# microfloat.net
KiCad netlist of a schematic drawn in EAGLE
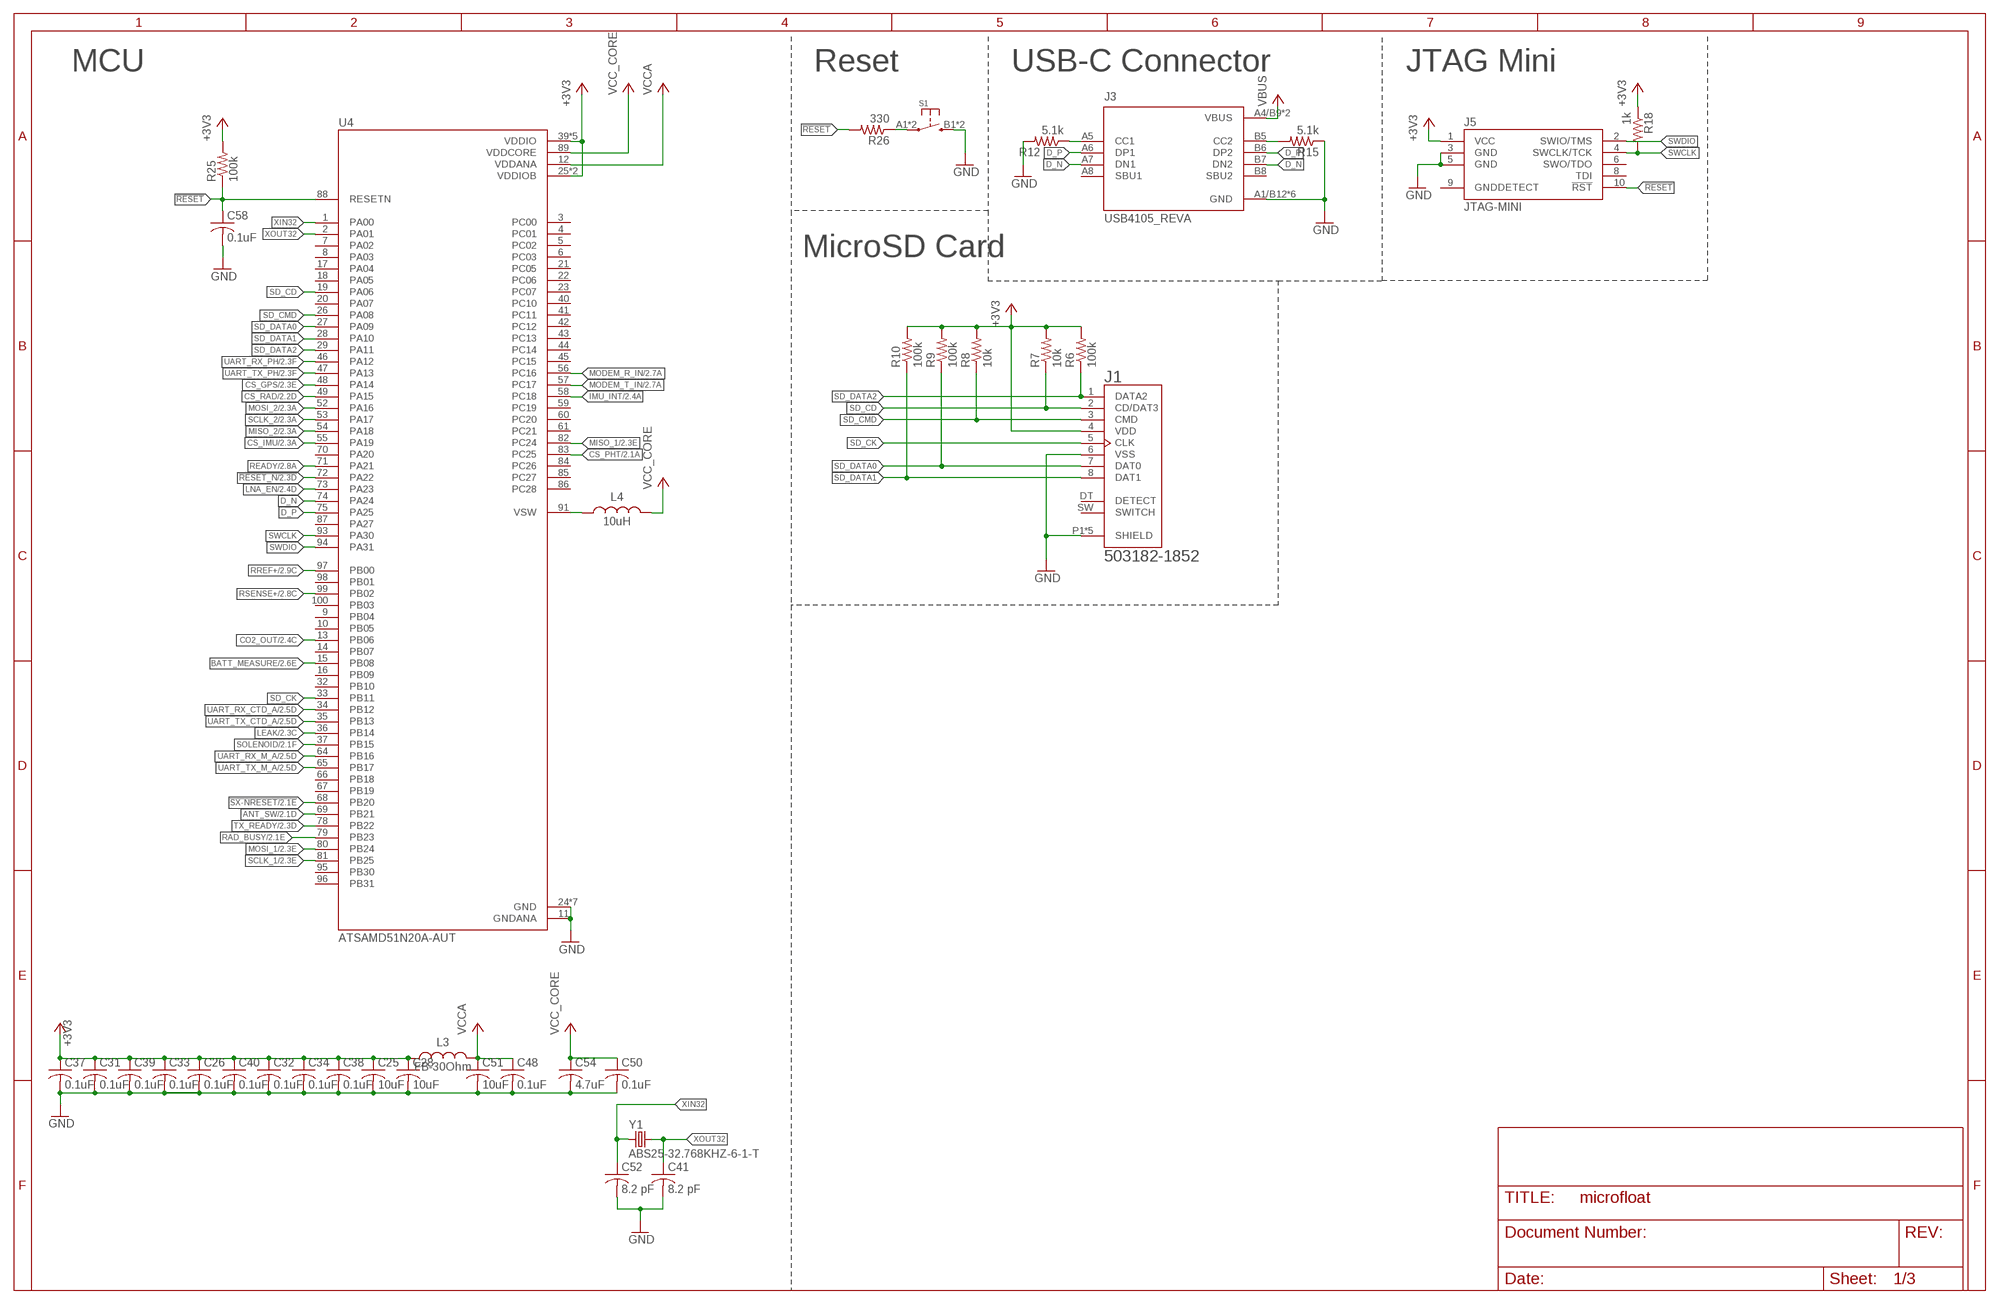
[diagram p0: schematic, sheet 1]
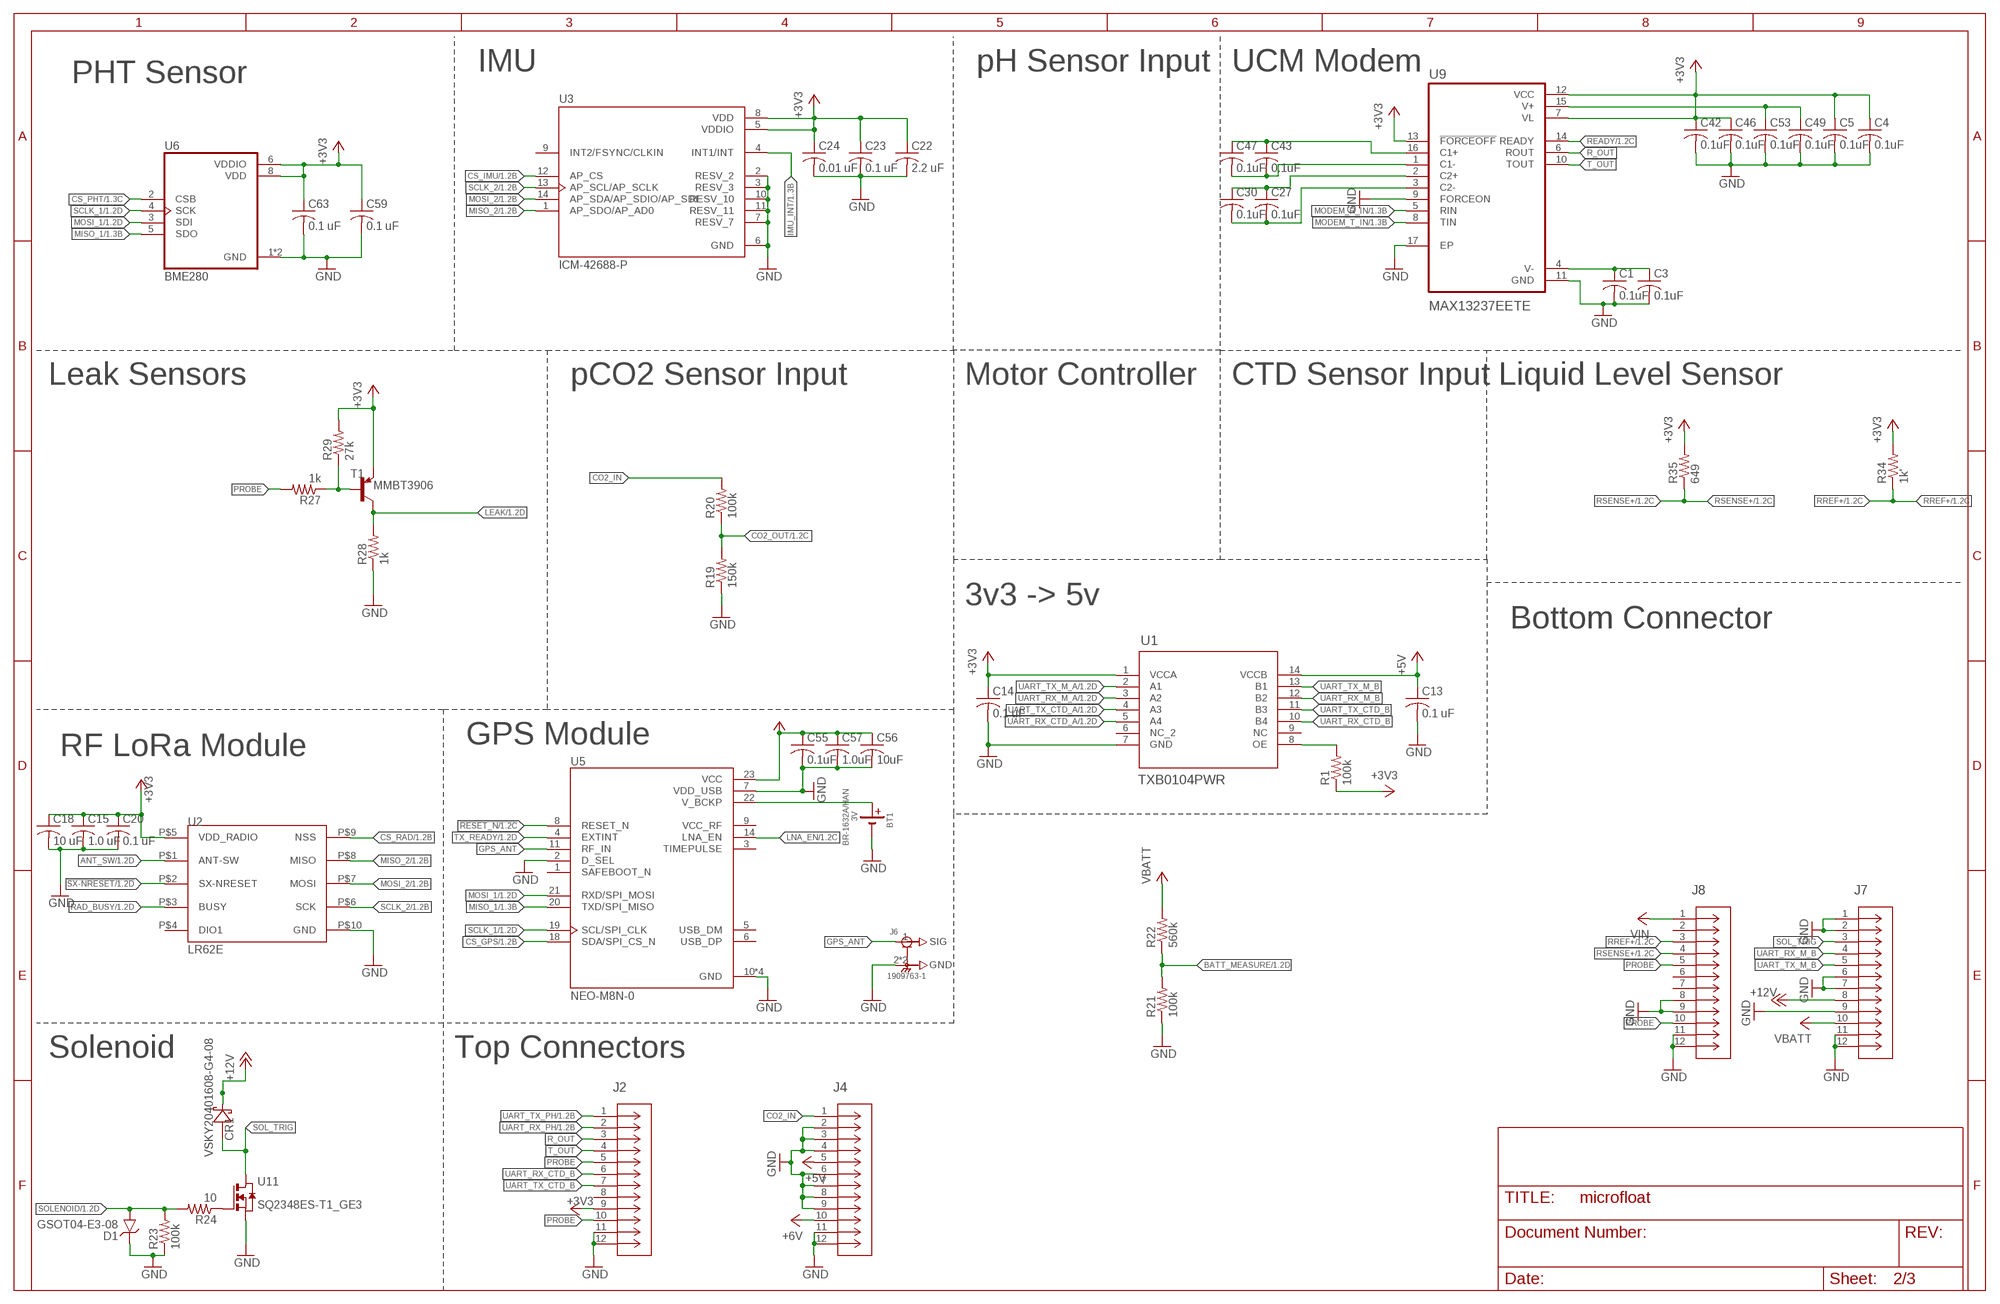
[diagram p1: schematic, sheet 2]
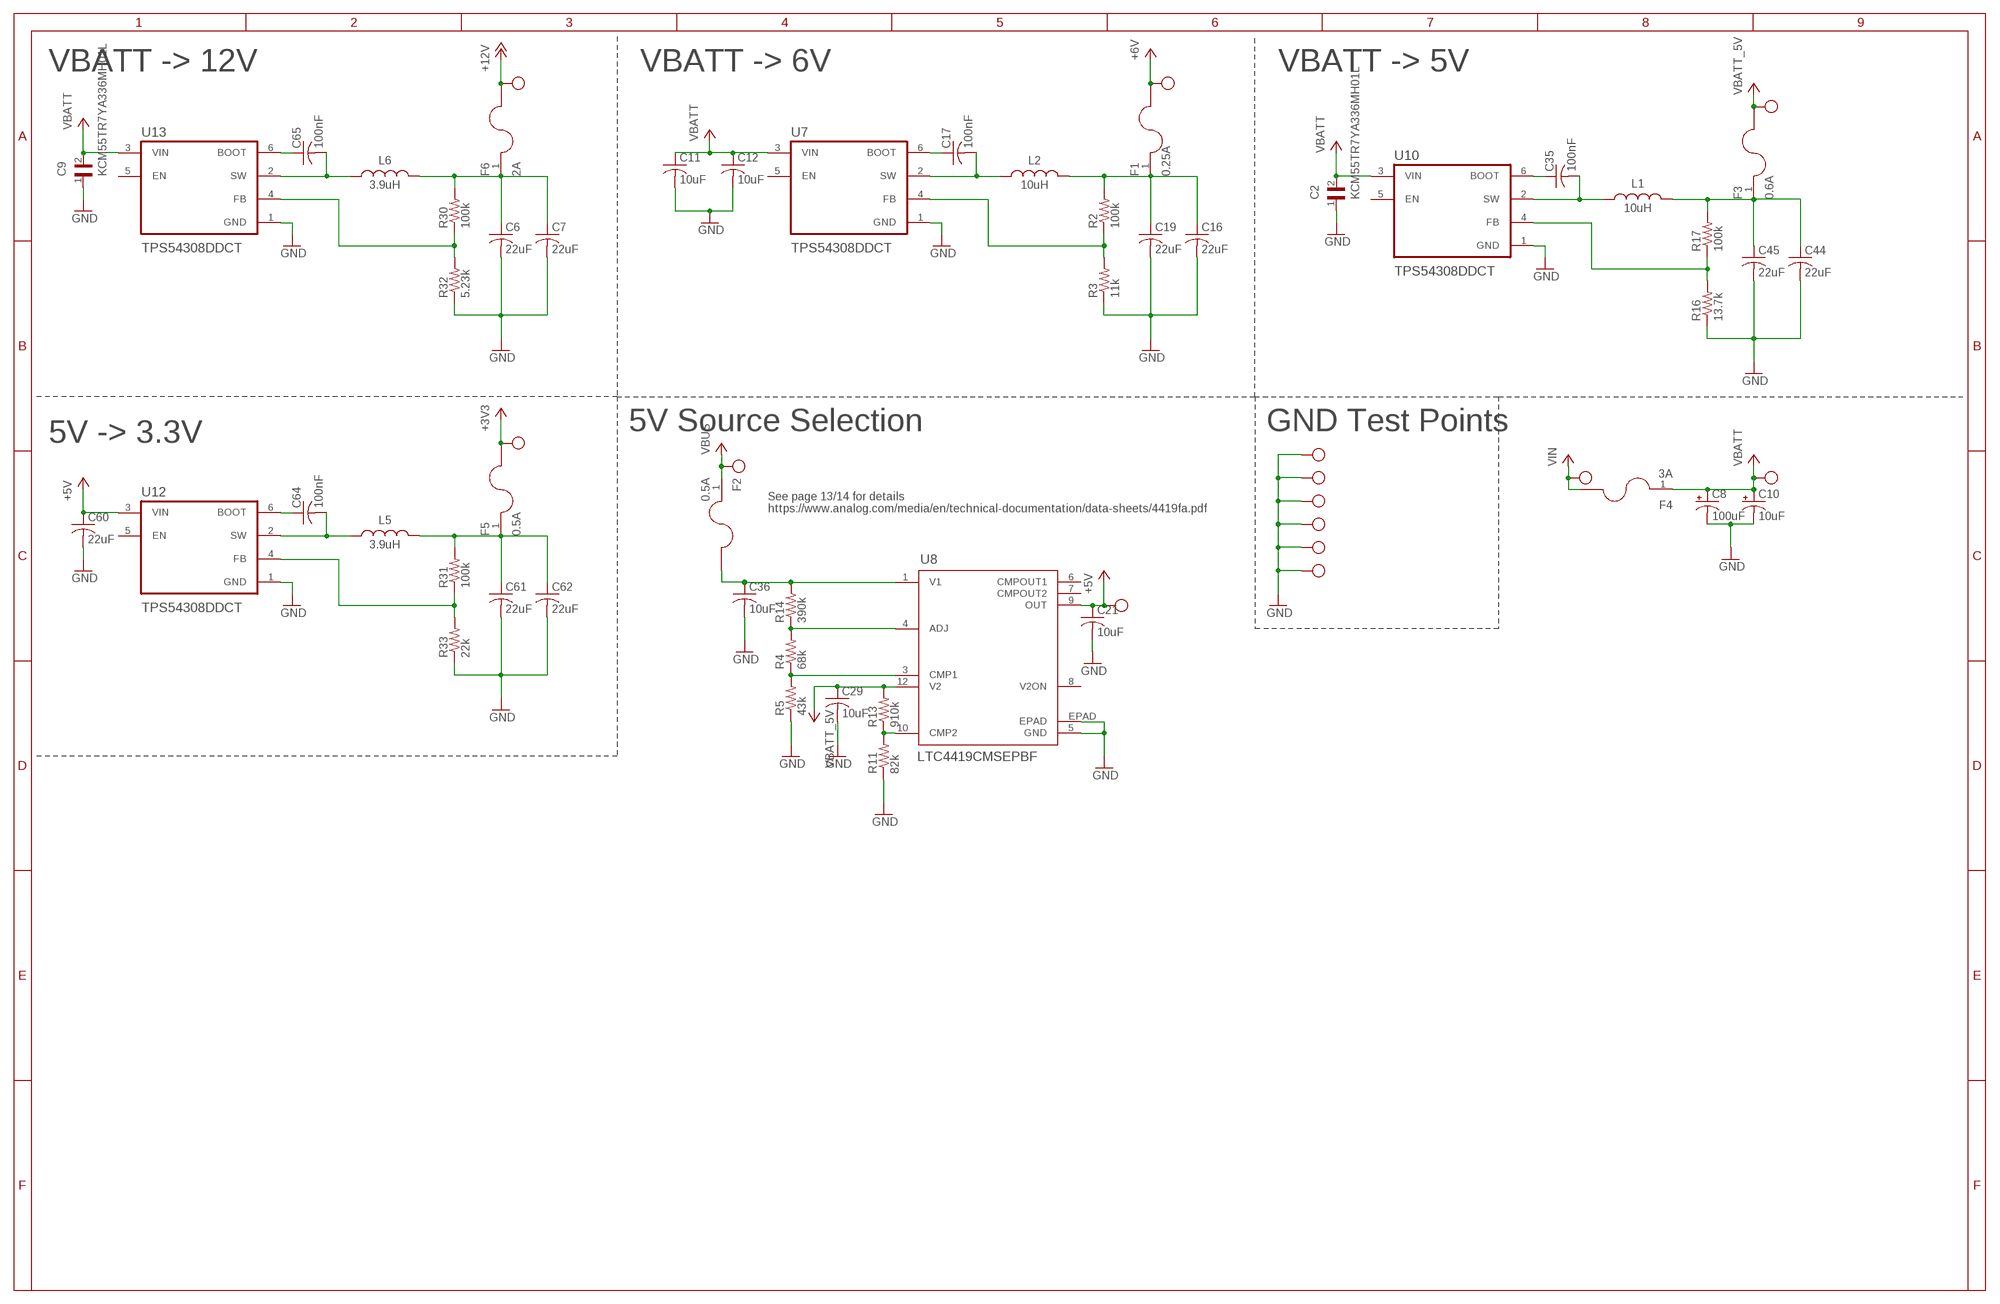
[diagram p2: schematic, sheet 3]

(export (version "E")
  (design (tool "Eeschema 10.0.6"))
  (components
    (comp (ref "C25")
      (value "10uF")
      (footprint "eagle-import:C0805")
      (fields (field (name "TOLERANCE") "5%") (field (name "VOLTAGE") "10V"))
      (libsource (lib "eagle-import") (part "C-USC0805"))
    )
    (comp (ref "C26")
      (value "0.1uF")
      (footprint "eagle-import:C0603")
      (fields (field (name "TOLERANCE") "5%") (field (name "VOLTAGE") "10V"))
      (libsource (lib "eagle-import") (part "C-USC0603"))
    )
    (comp (ref "C28")
      (value "10uF")
      (footprint "eagle-import:C0805")
      (fields (field (name "TOLERANCE") "5%") (field (name "VOLTAGE") "10V"))
      (libsource (lib "eagle-import") (part "C-USC0805"))
    )
    (comp (ref "C31")
      (value "0.1uF")
      (footprint "eagle-import:C0603")
      (fields (field (name "TOLERANCE") "5%") (field (name "VOLTAGE") "10V"))
      (libsource (lib "eagle-import") (part "C-USC0603"))
    )
    (comp (ref "C32")
      (value "0.1uF")
      (footprint "eagle-import:C0603")
      (fields (field (name "TOLERANCE") "5%") (field (name "VOLTAGE") "10V"))
      (libsource (lib "eagle-import") (part "C-USC0603"))
    )
    (comp (ref "C33")
      (value "0.1uF")
      (footprint "eagle-import:C0603")
      (fields (field (name "TOLERANCE") "5%") (field (name "VOLTAGE") "10V"))
      (libsource (lib "eagle-import") (part "C-USC0603"))
    )
    (comp (ref "C34")
      (value "0.1uF")
      (footprint "eagle-import:C0603")
      (fields (field (name "TOLERANCE") "5%") (field (name "VOLTAGE") "10V"))
      (libsource (lib "eagle-import") (part "C-USC0603"))
    )
    (comp (ref "C37")
      (value "0.1uF")
      (footprint "eagle-import:C0603")
      (fields (field (name "TOLERANCE") "5%") (field (name "VOLTAGE") "10V"))
      (libsource (lib "eagle-import") (part "C-USC0603"))
    )
    (comp (ref "C38")
      (value "0.1uF")
      (footprint "eagle-import:C0603")
      (fields (field (name "TOLERANCE") "5%") (field (name "VOLTAGE") "10V"))
      (libsource (lib "eagle-import") (part "C-USC0603"))
    )
    (comp (ref "C39")
      (value "0.1uF")
      (footprint "eagle-import:C0603")
      (fields (field (name "TOLERANCE") "5%") (field (name "VOLTAGE") "10V"))
      (libsource (lib "eagle-import") (part "C-USC0603"))
    )
    (comp (ref "C40")
      (value "0.1uF")
      (footprint "eagle-import:C0603")
      (fields (field (name "TOLERANCE") "5%") (field (name "VOLTAGE") "10V"))
      (libsource (lib "eagle-import") (part "C-USC0603"))
    )
    (comp (ref "C41")
      (value "8.2 pF")
      (footprint "eagle-import:C0603")
      (fields (field (name "TOLERANCE") "0.5%") (field (name "VOLTAGE") "10V"))
      (libsource (lib "eagle-import") (part "C-USC0603"))
    )
    (comp (ref "C48")
      (value "0.1uF")
      (footprint "eagle-import:C0603")
      (fields (field (name "TOLERANCE") "5%") (field (name "VOLTAGE") "10V"))
      (libsource (lib "eagle-import") (part "C-USC0603"))
    )
    (comp (ref "C50")
      (value "0.1uF")
      (footprint "eagle-import:C0603")
      (fields (field (name "TOLERANCE") "5%") (field (name "VOLTAGE") "10V"))
      (libsource (lib "eagle-import") (part "C-USC0603"))
    )
    (comp (ref "C51")
      (value "10uF")
      (footprint "eagle-import:C0805")
      (fields (field (name "TOLERANCE") "5%") (field (name "VOLTAGE") "10V"))
      (libsource (lib "eagle-import") (part "C-USC0805"))
    )
    (comp (ref "C52")
      (value "8.2 pF")
      (footprint "eagle-import:C0603")
      (fields (field (name "TOLERANCE") "0.5%") (field (name "VOLTAGE") "10V"))
      (libsource (lib "eagle-import") (part "C-USC0603"))
    )
    (comp (ref "C54")
      (value "4.7uF")
      (footprint "eagle-import:C0603")
      (fields (field (name "TOLERANCE") "5%") (field (name "VOLTAGE") "10V"))
      (libsource (lib "eagle-import") (part "C-USC0603"))
    )
    (comp (ref "C58")
      (value "0.1uF")
      (footprint "eagle-import:C0603")
      (fields (field (name "TOLERANCE") "5%") (field (name "VOLTAGE") "10V"))
      (libsource (lib "eagle-import") (part "C-USC0603"))
    )
    (comp (ref "J1")
      (value "503182-1852")
      (footprint "eagle-import:MOLEX_503182-1852")
      (libsource (lib "eagle-import") (part "503182-1852"))
    )
    (comp (ref "J3")
      (value "USB4105_REVA")
      (footprint "eagle-import:GCT_USB4105_REVA")
      (fields (field (name "MF") "Global Connector Technology") (field (name "MP") "USB4105"))
      (libsource (lib "eagle-import") (part "USB4105_REVA"))
    )
    (comp (ref "J5")
      (value "JTAG-MINI")
      (footprint "eagle-import:FTSH-105-01-F-D-K")
      (libsource (lib "eagle-import") (part "JTAG-MINI"))
    )
    (comp (ref "L3")
      (value "FB-30Ohm")
      (footprint "eagle-import:0805")
      (fields (field (name "DKPN") "490-1035-1-ND") (field (name "TOLERANCE") "25%"))
      (libsource (lib "eagle-import") (part "INDUCTOR_0805"))
    )
    (comp (ref "L4")
      (value "10uH")
      (footprint "eagle-import:78438336100")
      (fields (field (name "TOLERANCE") "10%"))
      (libsource (lib "eagle-import") (part "78438336100"))
    )
    (comp (ref "R6")
      (value "100k")
      (footprint "eagle-import:R0603")
      (fields (field (name "TOLERANCE") "1%"))
      (libsource (lib "eagle-import") (part "R-US_R0603"))
    )
    (comp (ref "R7")
      (value "10k")
      (footprint "eagle-import:R0603")
      (fields (field (name "TOLERANCE") "1%"))
      (libsource (lib "eagle-import") (part "R-US_R0603"))
    )
    (comp (ref "R8")
      (value "10k")
      (footprint "eagle-import:R0603")
      (fields (field (name "TOLERANCE") "1%"))
      (libsource (lib "eagle-import") (part "R-US_R0603"))
    )
    (comp (ref "R9")
      (value "100k")
      (footprint "eagle-import:R0603")
      (fields (field (name "TOLERANCE") "1%"))
      (libsource (lib "eagle-import") (part "R-US_R0603"))
    )
    (comp (ref "R10")
      (value "100k")
      (footprint "eagle-import:R0603")
      (fields (field (name "TOLERANCE") "1%"))
      (libsource (lib "eagle-import") (part "R-US_R0603"))
    )
    (comp (ref "R12")
      (value "5.1k")
      (footprint "eagle-import:R0603")
      (fields (field (name "TOLERANCE") "0.1%"))
      (libsource (lib "eagle-import") (part "R-US_R0603"))
    )
    (comp (ref "R15")
      (value "5.1k")
      (footprint "eagle-import:R0603")
      (fields (field (name "TOLERANCE") "0.1%"))
      (libsource (lib "eagle-import") (part "R-US_R0603"))
    )
    (comp (ref "R18")
      (value "1k")
      (footprint "eagle-import:R0603")
      (fields (field (name "TOLERANCE") "1%"))
      (libsource (lib "eagle-import") (part "R-US_R0603"))
    )
    (comp (ref "R25")
      (value "100k")
      (footprint "eagle-import:R0603")
      (fields (field (name "TOLERANCE") "1%"))
      (libsource (lib "eagle-import") (part "R-US_R0603"))
    )
    (comp (ref "R26")
      (value "330")
      (footprint "eagle-import:R0603")
      (fields (field (name "TOLERANCE") "1%"))
      (libsource (lib "eagle-import") (part "R-US_R0603"))
    )
    (comp (ref "S1")
      (value "BTN_10-XXSMD")
      (footprint "eagle-import:TACTILE_SWITCH_SMD_6.2MM_TALL")
      (libsource (lib "eagle-import") (part "BTN_10-XXSMD"))
    )
    (comp (ref "U4")
      (value "ATSAMD51N20A-AUT")
      (footprint "eagle-import:QFP50P1600X1600X120-100N")
      (fields (field (name "MF") "Microchip") (field (name "MP") "ATSAMD51N20A-AU"))
      (libsource (lib "eagle-import") (part "ATSAMD51N20A-AUT"))
    )
    (comp (ref "Y1")
      (value "ABS25-32.768KHZ-6-1-T")
      (footprint "eagle-import:XTAL_ABS25-32.768KHZ-6-1-T")
      (fields (field (name "DIGI-KEY_PART_NUMBER") "535-10241-1-ND") (field (name "MF") "Abracon"))
      (libsource (lib "eagle-import") (part "ABS25-32.768KHZ-6-1-T"))
    )
    (comp (ref "BT1")
      (value "BATTERY")
      (footprint "eagle-import:BR-1632A_HAN")
      (fields
        (field (name "MPN") "BR-1632A/HAN")
        (field (name "VOLTAGE") " 3V")
        (field (name "MANUFACTURER") "Panasonic - BSG")
      )
      (libsource (lib "eagle-import") (part "BATTERY"))
    )
    (comp (ref "C1")
      (value "0.1uF")
      (footprint "eagle-import:C0603")
      (fields (field (name "TOLERANCE") "5%") (field (name "VOLTAGE") "10V"))
      (libsource (lib "eagle-import") (part "C-USC0603"))
    )
    (comp (ref "C3")
      (value "0.1uF")
      (footprint "eagle-import:C0603")
      (fields (field (name "TOLERANCE") "5%") (field (name "VOLTAGE") "10V"))
      (libsource (lib "eagle-import") (part "C-USC0603"))
    )
    (comp (ref "C4")
      (value "0.1uF")
      (footprint "eagle-import:C0603")
      (fields (field (name "TOLERANCE") "5%") (field (name "VOLTAGE") "10V"))
      (libsource (lib "eagle-import") (part "C-USC0603"))
    )
    (comp (ref "C5")
      (value "0.1uF")
      (footprint "eagle-import:C0603")
      (fields (field (name "TOLERANCE") "5%") (field (name "VOLTAGE") "10V"))
      (libsource (lib "eagle-import") (part "C-USC0603"))
    )
    (comp (ref "C13")
      (value "0.1 uF")
      (footprint "eagle-import:C0603")
      (fields (field (name "TOLERANCE") "5%") (field (name "VOLTAGE") "10V"))
      (libsource (lib "eagle-import") (part "C-USC0603"))
    )
    (comp (ref "C14")
      (value "0.1 uF")
      (footprint "eagle-import:C0603")
      (fields (field (name "TOLERANCE") "5%") (field (name "VOLTAGE") "10V"))
      (libsource (lib "eagle-import") (part "C-USC0603"))
    )
    (comp (ref "C15")
      (value "1.0 uF")
      (footprint "eagle-import:C0603")
      (fields (field (name "TOLERANCE") "5%") (field (name "VOLTAGE") "10V"))
      (libsource (lib "eagle-import") (part "C-USC0603"))
    )
    (comp (ref "C18")
      (value "10 uF")
      (footprint "eagle-import:C0603")
      (fields (field (name "TOLERANCE") "5%") (field (name "VOLTAGE") "10V"))
      (libsource (lib "eagle-import") (part "C-USC0603"))
    )
    (comp (ref "C20")
      (value "0.1 uF")
      (footprint "eagle-import:C0603")
      (fields (field (name "TOLERANCE") "5%") (field (name "VOLTAGE") "10V"))
      (libsource (lib "eagle-import") (part "C-USC0603"))
    )
    (comp (ref "C22")
      (value "2.2 uF")
      (footprint "eagle-import:C0603")
      (fields (field (name "TOLERANCE") "5%") (field (name "VOLTAGE") "10V"))
      (libsource (lib "eagle-import") (part "C-USC0603"))
    )
    (comp (ref "C23")
      (value "0.1 uF")
      (footprint "eagle-import:C0603")
      (fields (field (name "TOLERANCE") "5%") (field (name "VOLTAGE") "10V"))
      (libsource (lib "eagle-import") (part "C-USC0603"))
    )
    (comp (ref "C24")
      (value "0.01 uF")
      (footprint "eagle-import:C0603")
      (fields (field (name "TOLERANCE") "5%") (field (name "VOLTAGE") "10V"))
      (libsource (lib "eagle-import") (part "C-USC0603"))
    )
    (comp (ref "C27")
      (value "0.1uF")
      (footprint "eagle-import:C0603")
      (fields (field (name "TOLERANCE") "5%") (field (name "VOLTAGE") "10V"))
      (libsource (lib "eagle-import") (part "C-USC0603"))
    )
    (comp (ref "C30")
      (value "0.1uF")
      (footprint "eagle-import:C0603")
      (fields (field (name "TOLERANCE") "5%") (field (name "VOLTAGE") "10V"))
      (libsource (lib "eagle-import") (part "C-USC0603"))
    )
    (comp (ref "C42")
      (value "0.1uF")
      (footprint "eagle-import:C0603")
      (fields (field (name "TOLERANCE") "5%") (field (name "VOLTAGE") "10V"))
      (libsource (lib "eagle-import") (part "C-USC0603"))
    )
    (comp (ref "C43")
      (value "0.1uF")
      (footprint "eagle-import:C0603")
      (fields (field (name "TOLERANCE") "5%") (field (name "VOLTAGE") "10V"))
      (libsource (lib "eagle-import") (part "C-USC0603"))
    )
    (comp (ref "C46")
      (value "0.1uF")
      (footprint "eagle-import:C0603")
      (fields (field (name "TOLERANCE") "5%") (field (name "VOLTAGE") "10V"))
      (libsource (lib "eagle-import") (part "C-USC0603"))
    )
    (comp (ref "C47")
      (value "0.1uF")
      (footprint "eagle-import:C0603")
      (fields (field (name "TOLERANCE") "5%") (field (name "VOLTAGE") "10V"))
      (libsource (lib "eagle-import") (part "C-USC0603"))
    )
    (comp (ref "C49")
      (value "0.1uF")
      (footprint "eagle-import:C0603")
      (fields (field (name "TOLERANCE") "5%") (field (name "VOLTAGE") "10V"))
      (libsource (lib "eagle-import") (part "C-USC0603"))
    )
    (comp (ref "C53")
      (value "0.1uF")
      (footprint "eagle-import:C0603")
      (fields (field (name "TOLERANCE") "5%") (field (name "VOLTAGE") "10V"))
      (libsource (lib "eagle-import") (part "C-USC0603"))
    )
    (comp (ref "C55")
      (value "0.1uF")
      (footprint "eagle-import:C0603")
      (fields (field (name "TOLERANCE") "5%") (field (name "VOLTAGE") "10V"))
      (libsource (lib "eagle-import") (part "C-USC0603"))
    )
    (comp (ref "C56")
      (value "10uF")
      (footprint "eagle-import:C0603")
      (fields (field (name "TOLERANCE") "5%") (field (name "VOLTAGE") "10V"))
      (libsource (lib "eagle-import") (part "C-USC0603"))
    )
    (comp (ref "C57")
      (value "1.0uF")
      (footprint "eagle-import:C0603")
      (fields (field (name "TOLERANCE") "5%") (field (name "VOLTAGE") "10V"))
      (libsource (lib "eagle-import") (part "C-USC0603"))
    )
    (comp (ref "C59")
      (value "0.1 uF")
      (footprint "eagle-import:C0603")
      (fields (field (name "TOLERANCE") "5%") (field (name "VOLTAGE") "10V"))
      (libsource (lib "eagle-import") (part "C-USC0603"))
    )
    (comp (ref "C63")
      (value "0.1 uF")
      (footprint "eagle-import:C0603")
      (fields (field (name "TOLERANCE") "5%") (field (name "VOLTAGE") "10V"))
      (libsource (lib "eagle-import") (part "C-USC0603"))
    )
    (comp (ref "CR1")
      (value "VSKY20401608-G4-08")
      (footprint "eagle-import:CLP1608-2L_VIS")
      (fields (field (name "COPYRIGHT") "Copyright (C) 2018 Accelerated Designs. All rights reserved"))
      (libsource (lib "eagle-import") (part "VSKY20401608-G4-08"))
    )
    (comp (ref "D1")
      (value "GSOT04-E3-08")
      (footprint "eagle-import:SOT-23-3")
      (libsource (lib "eagle-import") (part "GSOT04-E3-08"))
    )
    (comp (ref "J2")
      (value "1054291110")
      (footprint "eagle-import:CON_1054291110_MOL")
      (fields (field (name "COPYRIGHT") "Copyright (C) 2018 Accelerated Designs. All rights reserved"))
      (libsource (lib "eagle-import") (part "1054291110"))
    )
    (comp (ref "J4")
      (value "1054291110")
      (footprint "eagle-import:CON_1054291110_MOL")
      (fields (field (name "COPYRIGHT") "Copyright (C) 2018 Accelerated Designs. All rights reserved"))
      (libsource (lib "eagle-import") (part "1054291110"))
    )
    (comp (ref "J6")
      (value "1909763-1")
      (footprint "eagle-import:TE_1909763-1")
      (libsource (lib "eagle-import") (part "1909763-1"))
    )
    (comp (ref "J7")
      (value "1054291110")
      (footprint "eagle-import:CON_1054291110_MOL")
      (fields (field (name "COPYRIGHT") "Copyright (C) 2018 Accelerated Designs. All rights reserved"))
      (libsource (lib "eagle-import") (part "1054291110"))
    )
    (comp (ref "J8")
      (value "1054291110")
      (footprint "eagle-import:CON_1054291110_MOL")
      (fields (field (name "COPYRIGHT") "Copyright (C) 2018 Accelerated Designs. All rights reserved"))
      (libsource (lib "eagle-import") (part "1054291110"))
    )
    (comp (ref "R1")
      (value "100k")
      (footprint "eagle-import:R0603")
      (fields (field (name "TOLERANCE") "1%"))
      (libsource (lib "eagle-import") (part "R-US_R0603"))
    )
    (comp (ref "R19")
      (value "150k")
      (footprint "eagle-import:R0603")
      (fields (field (name "TOLERANCE") "0.1%"))
      (libsource (lib "eagle-import") (part "R-US_R0603"))
    )
    (comp (ref "R20")
      (value "100k")
      (footprint "eagle-import:R0603")
      (fields (field (name "TOLERANCE") "0.1%"))
      (libsource (lib "eagle-import") (part "R-US_R0603"))
    )
    (comp (ref "R21")
      (value "100k")
      (footprint "eagle-import:R0603")
      (fields (field (name "TOLERANCE") "0.1%"))
      (libsource (lib "eagle-import") (part "R-US_R0603"))
    )
    (comp (ref "R22")
      (value "560k")
      (footprint "eagle-import:R0603")
      (fields (field (name "TOLERANCE") "0.1%"))
      (libsource (lib "eagle-import") (part "R-US_R0603"))
    )
    (comp (ref "R23")
      (value "100k")
      (footprint "eagle-import:R0603")
      (fields (field (name "TOLERANCE") "1%"))
      (libsource (lib "eagle-import") (part "R-US_R0603"))
    )
    (comp (ref "R24")
      (value "10")
      (footprint "eagle-import:R0603")
      (fields (field (name "TOLERANCE") "1%"))
      (libsource (lib "eagle-import") (part "R-US_R0603"))
    )
    (comp (ref "R27")
      (value "1k")
      (footprint "eagle-import:R0603")
      (fields (field (name "TOLERANCE") "1%"))
      (libsource (lib "eagle-import") (part "R-US_R0603"))
    )
    (comp (ref "R28")
      (value "1k")
      (footprint "eagle-import:R0603")
      (fields (field (name "TOLERANCE") "1%"))
      (libsource (lib "eagle-import") (part "R-US_R0603"))
    )
    (comp (ref "R29")
      (value "27k")
      (footprint "eagle-import:R0603")
      (fields (field (name "TOLERANCE") "1%"))
      (libsource (lib "eagle-import") (part "R-US_R0603"))
    )
    (comp (ref "R34")
      (value "1k'")
      (footprint "eagle-import:R0603")
      (fields (field (name "TOLERANCE") "0.1%"))
      (libsource (lib "eagle-import") (part "R-US_R0603"))
    )
    (comp (ref "R35")
      (value "649")
      (footprint "eagle-import:R0603")
      (fields (field (name "TOLERANCE") "0.1%"))
      (libsource (lib "eagle-import") (part "R-US_R0603"))
    )
    (comp (ref "T1")
      (value "MMBT3906")
      (footprint "eagle-import:SOT23-BEC")
      (libsource (lib "eagle-import") (part "MMBT3906SOT23-BECBC807-40"))
    )
    (comp (ref "U1")
      (value "TXB0104PWR")
      (footprint "eagle-import:PW14")
      (libsource (lib "eagle-import") (part "TXB0104PWR"))
    )
    (comp (ref "U2")
      (value "LR62E")
      (footprint "eagle-import:LR62E")
      (libsource (lib "eagle-import") (part "LR62E"))
    )
    (comp (ref "U3")
      (value "ICM-42688-P")
      (footprint "eagle-import:PQFN50P300X250X97-14N")
      (libsource (lib "eagle-import") (part "ICM-42688-P"))
    )
    (comp (ref "U5")
      (value "NEO-M8N-0")
      (footprint "eagle-import:XCVR_NEO-M8N-0")
      (libsource (lib "eagle-import") (part "NEO-M8N-0"))
    )
    (comp (ref "U6")
      (value "BME280")
      (footprint "eagle-import:PSON65P250X250X100-8N")
      (libsource (lib "eagle-import") (part "BME280"))
    )
    (comp (ref "U9")
      (value "MAX13237EETE")
      (footprint "eagle-import:QFN80P500X500X80-17N")
      (fields
        (field (name "DIGI-KEY_PART_NUMBER") "MAX13237EETE+TTR-ND")
        (field (name "MF") "Maxim Integrated")
      )
      (libsource (lib "eagle-import") (part "MAX13237EETE"))
    )
    (comp (ref "U11")
      (value "SQ2348ES-T1_GE3")
      (footprint "eagle-import:SOT-23-3")
      (libsource (lib "eagle-import") (part "SQ2348ES-T1_GE3"))
    )
    (comp (ref "$$$$$$U$1")
      (value "TEST_POINT")
      (footprint "eagle-import:TEST_POINT")
      (libsource (lib "eagle-import") (part "TEST_POINT"))
    )
    (comp (ref "$$$$$$U$2")
      (value "TEST_POINT")
      (footprint "eagle-import:TEST_POINT")
      (libsource (lib "eagle-import") (part "TEST_POINT"))
    )
    (comp (ref "$$$$$$U$3")
      (value "TEST_POINT")
      (footprint "eagle-import:TEST_POINT")
      (libsource (lib "eagle-import") (part "TEST_POINT"))
    )
    (comp (ref "$$$$$$U$4")
      (value "TEST_POINT")
      (footprint "eagle-import:TEST_POINT")
      (libsource (lib "eagle-import") (part "TEST_POINT"))
    )
    (comp (ref "$$$$$$U$5")
      (value "TEST_POINT")
      (footprint "eagle-import:TEST_POINT")
      (libsource (lib "eagle-import") (part "TEST_POINT"))
    )
    (comp (ref "$$$$$$U$6")
      (value "TEST_POINT")
      (footprint "eagle-import:TEST_POINT")
      (libsource (lib "eagle-import") (part "TEST_POINT"))
    )
    (comp (ref "$$$$U$2")
      (value "TEST_POINT")
      (footprint "eagle-import:TEST_POINT")
      (libsource (lib "eagle-import") (part "TEST_POINT"))
    )
    (comp (ref "$$$$U$3")
      (value "TEST_POINT")
      (footprint "eagle-import:TEST_POINT")
      (libsource (lib "eagle-import") (part "TEST_POINT"))
    )
    (comp (ref "$$$$U$4")
      (value "TEST_POINT")
      (footprint "eagle-import:TEST_POINT")
      (libsource (lib "eagle-import") (part "TEST_POINT"))
    )
    (comp (ref "$$$$U$5")
      (value "TEST_POINT")
      (footprint "eagle-import:TEST_POINT")
      (libsource (lib "eagle-import") (part "TEST_POINT"))
    )
    (comp (ref "$$U$1")
      (value "TEST_POINT")
      (footprint "eagle-import:TEST_POINT")
      (libsource (lib "eagle-import") (part "TEST_POINT"))
    )
    (comp (ref "$$U$2")
      (value "TEST_POINT")
      (footprint "eagle-import:TEST_POINT")
      (libsource (lib "eagle-import") (part "TEST_POINT"))
    )
    (comp (ref "$$U$3")
      (value "TEST_POINT")
      (footprint "eagle-import:TEST_POINT")
      (libsource (lib "eagle-import") (part "TEST_POINT"))
    )
    (comp (ref "$$U$5")
      (value "TEST_POINT")
      (footprint "eagle-import:TEST_POINT")
      (libsource (lib "eagle-import") (part "TEST_POINT"))
    )
    (comp (ref "C2")
      (value "KCM55TR7YA336MH01L")
      (footprint "eagle-import:CAPC6153X500N")
      (fields (field (name "DIGI-KEY_PART_NUMBER") "490-16299-1-ND") (field (name "MF") "Murata"))
      (libsource (lib "eagle-import") (part "KCM55TR7YA336MH01L"))
    )
    (comp (ref "C6")
      (value "22uF")
      (footprint "eagle-import:C0805")
      (fields (field (name "TOLERANCE") "5%") (field (name "VOLTAGE") "16V"))
      (libsource (lib "eagle-import") (part "C-USC0805"))
    )
    (comp (ref "C7")
      (value "22uF")
      (footprint "eagle-import:C0805")
      (fields (field (name "TOLERANCE") "5%") (field (name "VOLTAGE") "16V"))
      (libsource (lib "eagle-import") (part "C-USC0805"))
    )
    (comp (ref "C8")
      (value "100uF")
      (footprint "eagle-import:E3,5-8")
      (fields (field (name "TOLERANCE") "20%") (field (name "VOLTAGE") "25V"))
      (libsource (lib "eagle-import") (part "CPOL-USE3.5-8"))
    )
    (comp (ref "C9")
      (value "KCM55TR7YA336MH01L")
      (footprint "eagle-import:CAPC6153X500N")
      (fields (field (name "DIGI-KEY_PART_NUMBER") "490-16299-1-ND") (field (name "MF") "Murata"))
      (libsource (lib "eagle-import") (part "KCM55TR7YA336MH01L"))
    )
    (comp (ref "C10")
      (value "10uF")
      (footprint "eagle-import:E2,5-5")
      (fields (field (name "TOLERANCE") "20%") (field (name "VOLTAGE") "25V"))
      (libsource (lib "eagle-import") (part "CPOL-USE2.5-5"))
    )
    (comp (ref "C11")
      (value "10uF")
      (footprint "eagle-import:C0805")
      (fields (field (name "TOLERANCE") "5%") (field (name "VOLTAGE") "35V"))
      (libsource (lib "eagle-import") (part "C-USC0805"))
    )
    (comp (ref "C12")
      (value "10uF")
      (footprint "eagle-import:C0805")
      (fields (field (name "TOLERANCE") "5%") (field (name "VOLTAGE") "35V"))
      (libsource (lib "eagle-import") (part "C-USC0805"))
    )
    (comp (ref "C16")
      (value "22uF")
      (footprint "eagle-import:C0805")
      (fields (field (name "TOLERANCE") "5%") (field (name "VOLTAGE") "16V"))
      (libsource (lib "eagle-import") (part "C-USC0805"))
    )
    (comp (ref "C17")
      (value "100nF")
      (footprint "eagle-import:C0603")
      (fields (field (name "TOLERANCE") "5%") (field (name "VOLTAGE") "16V"))
      (libsource (lib "eagle-import") (part "C-USC0603"))
    )
    (comp (ref "C19")
      (value "22uF")
      (footprint "eagle-import:C0805")
      (fields (field (name "TOLERANCE") "5%") (field (name "VOLTAGE") "16V"))
      (libsource (lib "eagle-import") (part "C-USC0805"))
    )
    (comp (ref "C21")
      (value "10uF")
      (footprint "eagle-import:C0603")
      (fields (field (name "TOLERANCE") "5%") (field (name "VOLTAGE") "10V"))
      (libsource (lib "eagle-import") (part "C-USC0603"))
    )
    (comp (ref "C29")
      (value "10uF")
      (footprint "eagle-import:C0603")
      (fields (field (name "TOLERANCE") "5%") (field (name "VOLTAGE") "10V"))
      (libsource (lib "eagle-import") (part "C-USC0603"))
    )
    (comp (ref "C35")
      (value "100nF")
      (footprint "eagle-import:C0603")
      (fields (field (name "TOLERANCE") "5%") (field (name "VOLTAGE") "16V"))
      (libsource (lib "eagle-import") (part "C-USC0603"))
    )
    (comp (ref "C36")
      (value "10uF")
      (footprint "eagle-import:C0603")
      (fields (field (name "TOLERANCE") "5%") (field (name "VOLTAGE") "10V"))
      (libsource (lib "eagle-import") (part "C-USC0603"))
    )
    (comp (ref "C44")
      (value "22uF")
      (footprint "eagle-import:C0603")
      (fields (field (name "TOLERANCE") "5%") (field (name "VOLTAGE") "10V"))
      (libsource (lib "eagle-import") (part "C-USC0603"))
    )
    (comp (ref "C45")
      (value "22uF")
      (footprint "eagle-import:C0603")
      (fields (field (name "TOLERANCE") "5%") (field (name "VOLTAGE") "10V"))
      (libsource (lib "eagle-import") (part "C-USC0603"))
    )
    (comp (ref "C60")
      (value "22uF")
      (footprint "eagle-import:C0603")
      (fields (field (name "TOLERANCE") "5%") (field (name "VOLTAGE") "10V"))
      (libsource (lib "eagle-import") (part "C-USC0603"))
    )
    (comp (ref "C61")
      (value "22uF")
      (footprint "eagle-import:C0603")
      (fields (field (name "TOLERANCE") "5%") (field (name "VOLTAGE") "10V"))
      (libsource (lib "eagle-import") (part "C-USC0603"))
    )
    (comp (ref "C62")
      (value "22uF")
      (footprint "eagle-import:C0603")
      (fields (field (name "TOLERANCE") "5%") (field (name "VOLTAGE") "10V"))
      (libsource (lib "eagle-import") (part "C-USC0603"))
    )
    (comp (ref "C64")
      (value "100nF")
      (footprint "eagle-import:C0603")
      (fields (field (name "TOLERANCE") "5%") (field (name "VOLTAGE") "10V"))
      (libsource (lib "eagle-import") (part "C-USC0603"))
    )
    (comp (ref "C65")
      (value "100nF")
      (footprint "eagle-import:C0603")
      (fields (field (name "TOLERANCE") "5%") (field (name "VOLTAGE") "16V"))
      (libsource (lib "eagle-import") (part "C-USC0603"))
    )
    (comp (ref "F1")
      (value "0.25A")
      (footprint "eagle-import:F1206")
      (libsource (lib "eagle-import") (part "SMD_FUSE1206"))
    )
    (comp (ref "F2")
      (value "0.5A")
      (footprint "eagle-import:F1206")
      (libsource (lib "eagle-import") (part "SMD_FUSE1206"))
    )
    (comp (ref "F3")
      (value "0.6A")
      (footprint "eagle-import:F1206")
      (libsource (lib "eagle-import") (part "SMD_FUSE1206"))
    )
    (comp (ref "F4")
      (value "3A")
      (footprint "eagle-import:F1206")
      (libsource (lib "eagle-import") (part "SMD_FUSE1206"))
    )
    (comp (ref "F5")
      (value "0.5A")
      (footprint "eagle-import:F1206")
      (libsource (lib "eagle-import") (part "SMD_FUSE1206"))
    )
    (comp (ref "F6")
      (value "2A")
      (footprint "eagle-import:F1206")
      (libsource (lib "eagle-import") (part "SMD_FUSE1206"))
    )
    (comp (ref "L1")
      (value "10uH")
      (footprint "eagle-import:78438336100")
      (fields (field (name "TOLERANCE") "10%"))
      (libsource (lib "eagle-import") (part "78438336100"))
    )
    (comp (ref "L2")
      (value "10uH")
      (footprint "eagle-import:78438336100")
      (fields (field (name "TOLERANCE") "10%"))
      (libsource (lib "eagle-import") (part "78438336100"))
    )
    (comp (ref "L5")
      (value "3.9uH")
      (footprint "eagle-import:SRR3818A-3R9Y")
      (fields (field (name "TOLERANCE") "10%"))
      (libsource (lib "eagle-import") (part "SRR3818A-3R9Y"))
    )
    (comp (ref "L6")
      (value "3.9uH")
      (footprint "eagle-import:SRR3818A-3R9Y")
      (fields (field (name "TOLERANCE") "10%"))
      (libsource (lib "eagle-import") (part "SRR3818A-3R9Y"))
    )
    (comp (ref "R2")
      (value "100k")
      (footprint "eagle-import:R0603")
      (fields (field (name "TOLERANCE") "1%"))
      (libsource (lib "eagle-import") (part "R-US_R0603"))
    )
    (comp (ref "R3")
      (value "11k")
      (footprint "eagle-import:R0603")
      (fields (field (name "TOLERANCE") "1%"))
      (libsource (lib "eagle-import") (part "R-US_R0603"))
    )
    (comp (ref "R4")
      (value "68k")
      (footprint "eagle-import:R0603")
      (fields (field (name "TOLERANCE") "0.1%"))
      (libsource (lib "eagle-import") (part "R-US_R0603"))
    )
    (comp (ref "R5")
      (value "43k")
      (footprint "eagle-import:R0603")
      (fields (field (name "TOLERANCE") "0.1%"))
      (libsource (lib "eagle-import") (part "R-US_R0603"))
    )
    (comp (ref "R11")
      (value "82k")
      (footprint "eagle-import:R0603")
      (fields (field (name "TOLERANCE") "0.1%"))
      (libsource (lib "eagle-import") (part "R-US_R0603"))
    )
    (comp (ref "R13")
      (value "910k")
      (footprint "eagle-import:R0603")
      (fields (field (name "TOLERANCE") "0.1%"))
      (libsource (lib "eagle-import") (part "R-US_R0603"))
    )
    (comp (ref "R14")
      (value "390k")
      (footprint "eagle-import:R0603")
      (fields (field (name "TOLERANCE") "0.1%"))
      (libsource (lib "eagle-import") (part "R-US_R0603"))
    )
    (comp (ref "R16")
      (value "13.7k")
      (footprint "eagle-import:R0603")
      (fields (field (name "TOLERANCE") "1%"))
      (libsource (lib "eagle-import") (part "R-US_R0603"))
    )
    (comp (ref "R17")
      (value "100k")
      (footprint "eagle-import:R0603")
      (fields (field (name "TOLERANCE") "1%"))
      (libsource (lib "eagle-import") (part "R-US_R0603"))
    )
    (comp (ref "R30")
      (value "100k")
      (footprint "eagle-import:R0603")
      (fields (field (name "TOLERANCE") "1%"))
      (libsource (lib "eagle-import") (part "R-US_R0603"))
    )
    (comp (ref "R31")
      (value "100k")
      (footprint "eagle-import:R0603")
      (fields (field (name "TOLERANCE") "1%"))
      (libsource (lib "eagle-import") (part "R-US_R0603"))
    )
    (comp (ref "R32")
      (value "5.23k")
      (footprint "eagle-import:R0603")
      (fields (field (name "TOLERANCE") "1%"))
      (libsource (lib "eagle-import") (part "R-US_R0603"))
    )
    (comp (ref "R33")
      (value "22k")
      (footprint "eagle-import:R0603")
      (fields (field (name "TOLERANCE") "1%"))
      (libsource (lib "eagle-import") (part "R-US_R0603"))
    )
    (comp (ref "U7")
      (value "TPS54308DDCT")
      (footprint "eagle-import:SOT95P280X110-6N")
      (fields (field (name "DIGI-KEY_PART_NUMBER") "296-47881-1-ND") (field (name "MF") "Texas Instruments"))
      (libsource (lib "eagle-import") (part "TPS54308DDCT"))
    )
    (comp (ref "U8")
      (value "LTC4419CMSEPBF")
      (footprint "eagle-import:MSE_12_ADI")
      (fields
        (field (name "MANUFACTURER_PART_NUMBER") "LTC4419CMSE#PBF")
        (field (name "COPYRIGHT") "Copyright (C) 2016 Accelerated Designs. All rights reserved")
      )
      (libsource (lib "eagle-import") (part "LTC4419CMSEPBF"))
    )
    (comp (ref "U10")
      (value "TPS54308DDCT")
      (footprint "eagle-import:SOT95P280X110-6N")
      (fields (field (name "DIGI-KEY_PART_NUMBER") "296-47881-1-ND") (field (name "MF") "Texas Instruments"))
      (libsource (lib "eagle-import") (part "TPS54308DDCT"))
    )
    (comp (ref "U12")
      (value "TPS54308DDCT")
      (footprint "eagle-import:SOT95P280X110-6N")
      (fields (field (name "DIGI-KEY_PART_NUMBER") "296-47881-1-ND") (field (name "MF") "Texas Instruments"))
      (libsource (lib "eagle-import") (part "TPS54308DDCT"))
    )
    (comp (ref "U13")
      (value "TPS54308DDCT")
      (footprint "eagle-import:SOT95P280X110-6N")
      (fields (field (name "DIGI-KEY_PART_NUMBER") "296-47881-1-ND") (field (name "MF") "Texas Instruments"))
      (libsource (lib "eagle-import") (part "TPS54308DDCT"))
    )
  )
  (nets
    (net (code "1") (name "+3V3") (class "Default")
      (node (ref "$$$$U$5") (pin "P$1") (pinfunction "P$1_P$1") (pintype "bidirectional"))
      (node (ref "C14") (pin "1") (pinfunction "1_1") (pintype "passive"))
      (node (ref "C15") (pin "1") (pinfunction "1_1") (pintype "passive"))
      (node (ref "C18") (pin "1") (pinfunction "1_1") (pintype "passive"))
      (node (ref "C20") (pin "1") (pinfunction "1_1") (pintype "passive"))
      (node (ref "C22") (pin "1") (pinfunction "1_1") (pintype "passive"))
      (node (ref "C23") (pin "1") (pinfunction "1_1") (pintype "passive"))
      (node (ref "C24") (pin "1") (pinfunction "1_1") (pintype "passive"))
      (node (ref "C25") (pin "1") (pinfunction "1_1") (pintype "passive"))
      (node (ref "C26") (pin "1") (pinfunction "1_1") (pintype "passive"))
      (node (ref "C28") (pin "1") (pinfunction "1_1") (pintype "passive"))
      (node (ref "C31") (pin "1") (pinfunction "1_1") (pintype "passive"))
      (node (ref "C32") (pin "1") (pinfunction "1_1") (pintype "passive"))
      (node (ref "C33") (pin "1") (pinfunction "1_1") (pintype "passive"))
      (node (ref "C34") (pin "1") (pinfunction "1_1") (pintype "passive"))
      (node (ref "C37") (pin "1") (pinfunction "1_1") (pintype "passive"))
      (node (ref "C38") (pin "1") (pinfunction "1_1") (pintype "passive"))
      (node (ref "C39") (pin "1") (pinfunction "1_1") (pintype "passive"))
      (node (ref "C4") (pin "1") (pinfunction "1_1") (pintype "passive"))
      (node (ref "C40") (pin "1") (pinfunction "1_1") (pintype "passive"))
      (node (ref "C42") (pin "1") (pinfunction "1_1") (pintype "passive"))
      (node (ref "C46") (pin "1") (pinfunction "1_1") (pintype "passive"))
      (node (ref "C5") (pin "1") (pinfunction "1_1") (pintype "passive"))
      (node (ref "C55") (pin "1") (pinfunction "1_1") (pintype "passive"))
      (node (ref "C56") (pin "1") (pinfunction "1_1") (pintype "passive"))
      (node (ref "C57") (pin "1") (pinfunction "1_1") (pintype "passive"))
      (node (ref "C59") (pin "1") (pinfunction "1_1") (pintype "passive"))
      (node (ref "C63") (pin "1") (pinfunction "1_1") (pintype "passive"))
      (node (ref "F5") (pin "2") (pinfunction "2_2") (pintype "passive"))
      (node (ref "J1") (pin "4") (pinfunction "VDD_4") (pintype "passive"))
      (node (ref "J2") (pin "9") (pinfunction "9_9") (pintype "passive"))
      (node (ref "J5") (pin "1") (pinfunction "VCC_1") (pintype "bidirectional"))
      (node (ref "L3") (pin "1") (pinfunction "1_1") (pintype "passive"))
      (node (ref "R1") (pin "1") (pinfunction "1_1") (pintype "passive"))
      (node (ref "R10") (pin "2") (pinfunction "2_2") (pintype "passive"))
      (node (ref "R18") (pin "1") (pinfunction "1_1") (pintype "passive"))
      (node (ref "R25") (pin "2") (pinfunction "2_2") (pintype "passive"))
      (node (ref "R29") (pin "2") (pinfunction "2_2") (pintype "passive"))
      (node (ref "R34") (pin "2") (pinfunction "2_2") (pintype "passive"))
      (node (ref "R35") (pin "2") (pinfunction "2_2") (pintype "passive"))
      (node (ref "R6") (pin "2") (pinfunction "2_2") (pintype "passive"))
      (node (ref "R7") (pin "2") (pinfunction "2_2") (pintype "passive"))
      (node (ref "R8") (pin "2") (pinfunction "2_2") (pintype "passive"))
      (node (ref "R9") (pin "2") (pinfunction "2_2") (pintype "passive"))
      (node (ref "T1") (pin "E") (pinfunction "E_E") (pintype "passive"))
      (node (ref "U1") (pin "1") (pinfunction "VCCA_1") (pintype "power_in"))
      (node (ref "U2") (pin "P$5") (pinfunction "VDD_RADIO_P$5") (pintype "passive"))
      (node (ref "U3") (pin "5") (pinfunction "VDDIO_5") (pintype "passive"))
      (node (ref "U3") (pin "8") (pinfunction "VDD_8") (pintype "passive"))
      (node (ref "U4") (pin "25") (pinfunction "VDDIOB_25") (pintype "power_in"))
      (node (ref "U4") (pin "30") (pinfunction "VDDIOB_30") (pintype "power_in"))
      (node (ref "U4") (pin "39") (pinfunction "VDDIO_39") (pintype "power_in"))
      (node (ref "U4") (pin "51") (pinfunction "VDDIO_51") (pintype "power_in"))
      (node (ref "U4") (pin "63") (pinfunction "VDDIO_63") (pintype "power_in"))
      (node (ref "U4") (pin "77") (pinfunction "VDDIO_77") (pintype "power_in"))
      (node (ref "U4") (pin "92") (pinfunction "VDDIO_92") (pintype "power_in"))
      (node (ref "U5") (pin "23") (pinfunction "VCC_23") (pintype "passive"))
      (node (ref "U6") (pin "6") (pinfunction "VDDIO_6") (pintype "passive"))
      (node (ref "U6") (pin "8") (pinfunction "VDD_8") (pintype "passive"))
      (node (ref "U9") (pin "12") (pinfunction "VCC_12") (pintype "passive"))
      (node (ref "U9") (pin "13") (pinfunction "~{FORCEOFF}_13") (pintype "passive"))
      (node (ref "U9") (pin "7") (pinfunction "VL_7") (pintype "passive"))
    )
    (net (code "2") (name "+5V") (class "Default")
      (node (ref "$$$$U$4") (pin "P$1") (pinfunction "P$1_P$1") (pintype "bidirectional"))
      (node (ref "C13") (pin "1") (pinfunction "1_1") (pintype "passive"))
      (node (ref "C21") (pin "1") (pinfunction "1_1") (pintype "passive"))
      (node (ref "C60") (pin "1") (pinfunction "1_1") (pintype "passive"))
      (node (ref "J4") (pin "5") (pinfunction "5_5") (pintype "passive"))
      (node (ref "U1") (pin "14") (pinfunction "VCCB_14") (pintype "power_in"))
      (node (ref "U12") (pin "3") (pinfunction "VIN_3") (pintype "input"))
      (node (ref "U8") (pin "9") (pinfunction "OUT_9") (pintype "output"))
    )
    (net (code "3") (name "+6V") (class "Default")
      (node (ref "$$$$U$3") (pin "P$1") (pinfunction "P$1_P$1") (pintype "bidirectional"))
      (node (ref "F1") (pin "2") (pinfunction "2_2") (pintype "passive"))
      (node (ref "J4") (pin "10") (pinfunction "10_10") (pintype "passive"))
    )
    (net (code "4") (name "+12V") (class "Default")
      (node (ref "$$U$5") (pin "P$1") (pinfunction "P$1_P$1") (pintype "bidirectional"))
      (node (ref "CR1") (pin "1") (pinfunction "11_1") (pintype "passive"))
      (node (ref "F6") (pin "2") (pinfunction "2_2") (pintype "passive"))
      (node (ref "J7") (pin "8") (pinfunction "8_8") (pintype "passive"))
    )
    (net (code "5") (name "ANT_SW") (class "Default")
      (node (ref "U2") (pin "P$1") (pinfunction "ANT-SW_P$1") (pintype "passive"))
      (node (ref "U4") (pin "69") (pinfunction "PB21_69") (pintype "bidirectional"))
    )
    (net (code "6") (name "BATT_MEASURE") (class "Default")
      (node (ref "R21") (pin "2") (pinfunction "2_2") (pintype "passive"))
      (node (ref "R22") (pin "1") (pinfunction "1_1") (pintype "passive"))
      (node (ref "U4") (pin "15") (pinfunction "PB08_15") (pintype "bidirectional"))
    )
    (net (code "7") (name "CO2_IN") (class "Default")
      (node (ref "J4") (pin "1") (pinfunction "1_1") (pintype "passive"))
      (node (ref "R20") (pin "2") (pinfunction "2_2") (pintype "passive"))
    )
    (net (code "8") (name "CO2_OUT") (class "Default")
      (node (ref "R19") (pin "2") (pinfunction "2_2") (pintype "passive"))
      (node (ref "R20") (pin "1") (pinfunction "1_1") (pintype "passive"))
      (node (ref "U4") (pin "13") (pinfunction "PB06_13") (pintype "bidirectional"))
    )
    (net (code "9") (name "CS_GPS") (class "Default")
      (node (ref "U4") (pin "48") (pinfunction "PA14_48") (pintype "bidirectional"))
      (node (ref "U5") (pin "18") (pinfunction "SDA/SPI_CS_N_18") (pintype "passive"))
    )
    (net (code "10") (name "CS_IMU") (class "Default")
      (node (ref "U3") (pin "12") (pinfunction "AP_CS_12") (pintype "passive"))
      (node (ref "U4") (pin "55") (pinfunction "PA19_55") (pintype "bidirectional"))
    )
    (net (code "11") (name "CS_PHT") (class "Default")
      (node (ref "U4") (pin "83") (pinfunction "PC25_83") (pintype "bidirectional"))
      (node (ref "U6") (pin "2") (pinfunction "CSB_2") (pintype "passive"))
    )
    (net (code "12") (name "CS_RAD") (class "Default")
      (node (ref "U2") (pin "P$9") (pinfunction "NSS_P$9") (pintype "passive"))
      (node (ref "U4") (pin "49") (pinfunction "PA15_49") (pintype "bidirectional"))
    )
    (net (code "13") (name "D_N") (class "Default")
      (node (ref "J3") (pin "A7") (pinfunction "DN1_A7") (pintype "bidirectional"))
      (node (ref "J3") (pin "B7") (pinfunction "DN2_B7") (pintype "bidirectional"))
      (node (ref "U4") (pin "74") (pinfunction "PA24_74") (pintype "bidirectional"))
    )
    (net (code "14") (name "D_P") (class "Default")
      (node (ref "J3") (pin "A6") (pinfunction "DP1_A6") (pintype "bidirectional"))
      (node (ref "J3") (pin "B6") (pinfunction "DP2_B6") (pintype "bidirectional"))
      (node (ref "U4") (pin "75") (pinfunction "PA25_75") (pintype "bidirectional"))
    )
    (net (code "15") (name "GND") (class "Default")
      (node (ref "$$$$$$U$4") (pin "P$1") (pinfunction "P$1_P$1") (pintype "bidirectional"))
      (node (ref "$$$$$$U$5") (pin "P$1") (pinfunction "P$1_P$1") (pintype "bidirectional"))
      (node (ref "$$$$U$2") (pin "P$1") (pinfunction "P$1_P$1") (pintype "bidirectional"))
      (node (ref "$$U$1") (pin "P$1") (pinfunction "P$1_P$1") (pintype "bidirectional"))
      (node (ref "$$U$2") (pin "P$1") (pinfunction "P$1_P$1") (pintype "bidirectional"))
      (node (ref "$$U$3") (pin "P$1") (pinfunction "P$1_P$1") (pintype "bidirectional"))
      (node (ref "BT1") (pin "-") (pinfunction "MINUS_-") (pintype "power_in"))
      (node (ref "C1") (pin "2") (pinfunction "2_2") (pintype "passive"))
      (node (ref "C10") (pin "-") (pinfunction "-_-") (pintype "passive"))
      (node (ref "C11") (pin "2") (pinfunction "2_2") (pintype "passive"))
      (node (ref "C12") (pin "2") (pinfunction "2_2") (pintype "passive"))
      (node (ref "C13") (pin "2") (pinfunction "2_2") (pintype "passive"))
      (node (ref "C14") (pin "2") (pinfunction "2_2") (pintype "passive"))
      (node (ref "C15") (pin "2") (pinfunction "2_2") (pintype "passive"))
      (node (ref "C16") (pin "2") (pinfunction "2_2") (pintype "passive"))
      (node (ref "C18") (pin "2") (pinfunction "2_2") (pintype "passive"))
      (node (ref "C19") (pin "2") (pinfunction "2_2") (pintype "passive"))
      (node (ref "C2") (pin "1") (pinfunction "1_1") (pintype "passive"))
      (node (ref "C20") (pin "2") (pinfunction "2_2") (pintype "passive"))
      (node (ref "C21") (pin "2") (pinfunction "2_2") (pintype "passive"))
      (node (ref "C22") (pin "2") (pinfunction "2_2") (pintype "passive"))
      (node (ref "C23") (pin "2") (pinfunction "2_2") (pintype "passive"))
      (node (ref "C24") (pin "2") (pinfunction "2_2") (pintype "passive"))
      (node (ref "C25") (pin "2") (pinfunction "2_2") (pintype "passive"))
      (node (ref "C26") (pin "2") (pinfunction "2_2") (pintype "passive"))
      (node (ref "C28") (pin "2") (pinfunction "2_2") (pintype "passive"))
      (node (ref "C29") (pin "2") (pinfunction "2_2") (pintype "passive"))
      (node (ref "C3") (pin "2") (pinfunction "2_2") (pintype "passive"))
      (node (ref "C31") (pin "2") (pinfunction "2_2") (pintype "passive"))
      (node (ref "C32") (pin "2") (pinfunction "2_2") (pintype "passive"))
      (node (ref "C33") (pin "2") (pinfunction "2_2") (pintype "passive"))
      (node (ref "C34") (pin "2") (pinfunction "2_2") (pintype "passive"))
      (node (ref "C36") (pin "2") (pinfunction "2_2") (pintype "passive"))
      (node (ref "C37") (pin "2") (pinfunction "2_2") (pintype "passive"))
      (node (ref "C38") (pin "2") (pinfunction "2_2") (pintype "passive"))
      (node (ref "C39") (pin "2") (pinfunction "2_2") (pintype "passive"))
      (node (ref "C4") (pin "2") (pinfunction "2_2") (pintype "passive"))
      (node (ref "C40") (pin "2") (pinfunction "2_2") (pintype "passive"))
      (node (ref "C41") (pin "2") (pinfunction "2_2") (pintype "passive"))
      (node (ref "C42") (pin "2") (pinfunction "2_2") (pintype "passive"))
      (node (ref "C44") (pin "2") (pinfunction "2_2") (pintype "passive"))
      (node (ref "C45") (pin "2") (pinfunction "2_2") (pintype "passive"))
      (node (ref "C46") (pin "2") (pinfunction "2_2") (pintype "passive"))
      (node (ref "C48") (pin "2") (pinfunction "2_2") (pintype "passive"))
      (node (ref "C49") (pin "2") (pinfunction "2_2") (pintype "passive"))
      (node (ref "C5") (pin "2") (pinfunction "2_2") (pintype "passive"))
      (node (ref "C50") (pin "2") (pinfunction "2_2") (pintype "passive"))
      (node (ref "C51") (pin "2") (pinfunction "2_2") (pintype "passive"))
      (node (ref "C52") (pin "2") (pinfunction "2_2") (pintype "passive"))
      (node (ref "C53") (pin "2") (pinfunction "2_2") (pintype "passive"))
      (node (ref "C54") (pin "2") (pinfunction "2_2") (pintype "passive"))
      (node (ref "C55") (pin "2") (pinfunction "2_2") (pintype "passive"))
      (node (ref "C56") (pin "2") (pinfunction "2_2") (pintype "passive"))
      (node (ref "C57") (pin "2") (pinfunction "2_2") (pintype "passive"))
      (node (ref "C58") (pin "2") (pinfunction "2_2") (pintype "passive"))
      (node (ref "C59") (pin "2") (pinfunction "2_2") (pintype "passive"))
      (node (ref "C6") (pin "2") (pinfunction "2_2") (pintype "passive"))
      (node (ref "C60") (pin "2") (pinfunction "2_2") (pintype "passive"))
      (node (ref "C61") (pin "2") (pinfunction "2_2") (pintype "passive"))
      (node (ref "C62") (pin "2") (pinfunction "2_2") (pintype "passive"))
      (node (ref "C63") (pin "2") (pinfunction "2_2") (pintype "passive"))
      (node (ref "C7") (pin "2") (pinfunction "2_2") (pintype "passive"))
      (node (ref "C8") (pin "-") (pinfunction "-_-") (pintype "passive"))
      (node (ref "C9") (pin "1") (pinfunction "1_1") (pintype "passive"))
      (node (ref "D1") (pin "3") (pinfunction "C_3") (pintype "passive"))
      (node (ref "J1") (pin "6") (pinfunction "VSS_6") (pintype "passive"))
      (node (ref "J1") (pin "P1") (pinfunction "SHIELD_P1") (pintype "passive"))
      (node (ref "J1") (pin "P2") (pinfunction "SHIELD_P2") (pintype "passive"))
      (node (ref "J1") (pin "P3") (pinfunction "SHIELD_P3") (pintype "passive"))
      (node (ref "J1") (pin "P4") (pinfunction "SHIELD_P4") (pintype "passive"))
      (node (ref "J1") (pin "P5") (pinfunction "SHIELD_P5") (pintype "passive"))
      (node (ref "J2") (pin "11") (pinfunction "11_11") (pintype "passive"))
      (node (ref "J2") (pin "12") (pinfunction "12_12") (pintype "passive"))
      (node (ref "J3") (pin "A1/B12") (pinfunction "GND_A1/B12") (pintype "power_in"))
      (node (ref "J3") (pin "B1/A12") (pinfunction "GND_B1/A12") (pintype "power_in"))
      (node (ref "J3") (pin "G1") (pinfunction "GND_G1") (pintype "power_in"))
      (node (ref "J3") (pin "G2") (pinfunction "GND_G2") (pintype "power_in"))
      (node (ref "J3") (pin "G3") (pinfunction "GND_G3") (pintype "power_in"))
      (node (ref "J3") (pin "G4") (pinfunction "GND_G4") (pintype "power_in"))
      (node (ref "J4") (pin "11") (pinfunction "11_11") (pintype "passive"))
      (node (ref "J4") (pin "12") (pinfunction "12_12") (pintype "passive"))
      (node (ref "J4") (pin "2") (pinfunction "2_2") (pintype "passive"))
      (node (ref "J4") (pin "3") (pinfunction "3_3") (pintype "passive"))
      (node (ref "J4") (pin "4") (pinfunction "4_4") (pintype "passive"))
      (node (ref "J4") (pin "6") (pinfunction "6_6") (pintype "passive"))
      (node (ref "J4") (pin "7") (pinfunction "7_7") (pintype "passive"))
      (node (ref "J4") (pin "8") (pinfunction "8_8") (pintype "passive"))
      (node (ref "J4") (pin "9") (pinfunction "9_9") (pintype "passive"))
      (node (ref "J5") (pin "3") (pinfunction "GND_3") (pintype "bidirectional"))
      (node (ref "J5") (pin "5") (pinfunction "GND_5") (pintype "bidirectional"))
      (node (ref "J6") (pin "2") (pinfunction "GND_2") (pintype "passive"))
      (node (ref "J6") (pin "3") (pinfunction "GND_3") (pintype "passive"))
      (node (ref "J7") (pin "1") (pinfunction "1_1") (pintype "passive"))
      (node (ref "J7") (pin "11") (pinfunction "11_11") (pintype "passive"))
      (node (ref "J7") (pin "12") (pinfunction "12_12") (pintype "passive"))
      (node (ref "J7") (pin "2") (pinfunction "2_2") (pintype "passive"))
      (node (ref "J7") (pin "6") (pinfunction "6_6") (pintype "passive"))
      (node (ref "J7") (pin "7") (pinfunction "7_7") (pintype "passive"))
      (node (ref "J7") (pin "9") (pinfunction "9_9") (pintype "passive"))
      (node (ref "J8") (pin "11") (pinfunction "11_11") (pintype "passive"))
      (node (ref "J8") (pin "12") (pinfunction "12_12") (pintype "passive"))
      (node (ref "J8") (pin "8") (pinfunction "8_8") (pintype "passive"))
      (node (ref "J8") (pin "9") (pinfunction "9_9") (pintype "passive"))
      (node (ref "R11") (pin "1") (pinfunction "1_1") (pintype "passive"))
      (node (ref "R12") (pin "2") (pinfunction "2_2") (pintype "passive"))
      (node (ref "R15") (pin "1") (pinfunction "1_1") (pintype "passive"))
      (node (ref "R16") (pin "1") (pinfunction "1_1") (pintype "passive"))
      (node (ref "R19") (pin "1") (pinfunction "1_1") (pintype "passive"))
      (node (ref "R21") (pin "1") (pinfunction "1_1") (pintype "passive"))
      (node (ref "R23") (pin "1") (pinfunction "1_1") (pintype "passive"))
      (node (ref "R28") (pin "1") (pinfunction "1_1") (pintype "passive"))
      (node (ref "R3") (pin "1") (pinfunction "1_1") (pintype "passive"))
      (node (ref "R32") (pin "1") (pinfunction "1_1") (pintype "passive"))
      (node (ref "R33") (pin "1") (pinfunction "1_1") (pintype "passive"))
      (node (ref "R5") (pin "1") (pinfunction "1_1") (pintype "passive"))
      (node (ref "S1") (pin "B1") (pinfunction "S_B1") (pintype "passive"))
      (node (ref "S1") (pin "B2") (pinfunction "S_B2") (pintype "passive"))
      (node (ref "U1") (pin "7") (pinfunction "GND_7") (pintype "power_in"))
      (node (ref "U10") (pin "1") (pinfunction "GND_1") (pintype "power_in"))
      (node (ref "U11") (pin "2") (pinfunction "S_2") (pintype "passive"))
      (node (ref "U12") (pin "1") (pinfunction "GND_1") (pintype "power_in"))
      (node (ref "U13") (pin "1") (pinfunction "GND_1") (pintype "power_in"))
      (node (ref "U2") (pin "P$10") (pinfunction "GND_P$10") (pintype "passive"))
      (node (ref "U3") (pin "10") (pinfunction "RESV_10_10") (pintype "passive"))
      (node (ref "U3") (pin "11") (pinfunction "RESV_11_11") (pintype "passive"))
      (node (ref "U3") (pin "2") (pinfunction "RESV_2_2") (pintype "passive"))
      (node (ref "U3") (pin "3") (pinfunction "RESV_3_3") (pintype "passive"))
      (node (ref "U3") (pin "6") (pinfunction "GND_6") (pintype "passive"))
      (node (ref "U3") (pin "7") (pinfunction "RESV_7_7") (pintype "passive"))
      (node (ref "U4") (pin "11") (pinfunction "GNDANA_11") (pintype "power_in"))
      (node (ref "U4") (pin "24") (pinfunction "GND_24") (pintype "power_in"))
      (node (ref "U4") (pin "31") (pinfunction "GND_31") (pintype "power_in"))
      (node (ref "U4") (pin "38") (pinfunction "GND_38") (pintype "power_in"))
      (node (ref "U4") (pin "50") (pinfunction "GND_50") (pintype "power_in"))
      (node (ref "U4") (pin "62") (pinfunction "GND_62") (pintype "power_in"))
      (node (ref "U4") (pin "76") (pinfunction "GND_76") (pintype "power_in"))
      (node (ref "U4") (pin "90") (pinfunction "GND_90") (pintype "power_in"))
      (node (ref "U5") (pin "10") (pinfunction "GND_10") (pintype "passive"))
      (node (ref "U5") (pin "12") (pinfunction "GND_12") (pintype "passive"))
      (node (ref "U5") (pin "13") (pinfunction "GND_13") (pintype "passive"))
      (node (ref "U5") (pin "2") (pinfunction "D_SEL_2") (pintype "passive"))
      (node (ref "U5") (pin "24") (pinfunction "GND_24") (pintype "passive"))
      (node (ref "U5") (pin "7") (pinfunction "VDD_USB_7") (pintype "passive"))
      (node (ref "U6") (pin "1") (pinfunction "GND_1") (pintype "passive"))
      (node (ref "U6") (pin "7") (pinfunction "GND_7") (pintype "passive"))
      (node (ref "U7") (pin "1") (pinfunction "GND_1") (pintype "power_in"))
      (node (ref "U8") (pin "5") (pinfunction "GND_5") (pintype "passive"))
      (node (ref "U8") (pin "EPAD") (pinfunction "EPAD_EPAD") (pintype "passive"))
      (node (ref "U9") (pin "11") (pinfunction "GND_11") (pintype "passive"))
      (node (ref "U9") (pin "17") (pinfunction "EP_17") (pintype "passive"))
      (node (ref "U9") (pin "9") (pinfunction "FORCEON_9") (pintype "passive"))
    )
    (net (code "16") (name "GPS_ANT") (class "Default")
      (node (ref "J6") (pin "1") (pinfunction "SIG_1") (pintype "passive"))
      (node (ref "U5") (pin "11") (pinfunction "RF_IN_11") (pintype "passive"))
    )
    (net (code "17") (name "IMU_INT") (class "Default")
      (node (ref "U3") (pin "4") (pinfunction "INT1/INT_4") (pintype "passive"))
      (node (ref "U4") (pin "58") (pinfunction "PC18_58") (pintype "bidirectional"))
    )
    (net (code "18") (name "LEAK") (class "Default")
      (node (ref "R28") (pin "2") (pinfunction "2_2") (pintype "passive"))
      (node (ref "T1") (pin "C") (pinfunction "C_C") (pintype "passive"))
      (node (ref "U4") (pin "36") (pinfunction "PB14_36") (pintype "bidirectional"))
    )
    (net (code "19") (name "LNA_EN") (class "Default")
      (node (ref "U4") (pin "73") (pinfunction "PA23_73") (pintype "bidirectional"))
      (node (ref "U5") (pin "14") (pinfunction "LNA_EN_14") (pintype "passive"))
    )
    (net (code "20") (name "MISO_1") (class "Default")
      (node (ref "U4") (pin "82") (pinfunction "PC24_82") (pintype "bidirectional"))
      (node (ref "U5") (pin "20") (pinfunction "TXD/SPI_MISO_20") (pintype "passive"))
      (node (ref "U6") (pin "5") (pinfunction "SDO_5") (pintype "passive"))
    )
    (net (code "21") (name "MISO_2") (class "Default")
      (node (ref "U2") (pin "P$8") (pinfunction "MISO_P$8") (pintype "passive"))
      (node (ref "U3") (pin "1") (pinfunction "AP_SDO/AP_AD0_1") (pintype "passive"))
      (node (ref "U4") (pin "54") (pinfunction "PA18_54") (pintype "bidirectional"))
    )
    (net (code "22") (name "MODEM_R_IN") (class "Default")
      (node (ref "U4") (pin "56") (pinfunction "PC16_56") (pintype "bidirectional"))
      (node (ref "U9") (pin "5") (pinfunction "RIN_5") (pintype "passive"))
    )
    (net (code "23") (name "MODEM_T_IN") (class "Default")
      (node (ref "U4") (pin "57") (pinfunction "PC17_57") (pintype "bidirectional"))
      (node (ref "U9") (pin "8") (pinfunction "TIN_8") (pintype "passive"))
    )
    (net (code "24") (name "MOSI_1") (class "Default")
      (node (ref "U4") (pin "80") (pinfunction "PB24_80") (pintype "bidirectional"))
      (node (ref "U5") (pin "21") (pinfunction "RXD/SPI_MOSI_21") (pintype "passive"))
      (node (ref "U6") (pin "3") (pinfunction "SDI_3") (pintype "passive"))
    )
    (net (code "25") (name "MOSI_2") (class "Default")
      (node (ref "U2") (pin "P$7") (pinfunction "MOSI_P$7") (pintype "passive"))
      (node (ref "U3") (pin "14") (pinfunction "AP_SDA/AP_SDIO/AP_SDI_14") (pintype "passive"))
      (node (ref "U4") (pin "52") (pinfunction "PA16_52") (pintype "bidirectional"))
    )
    (net (code "26") (name "Net-(BT1-PLUS)") (class "Default")
      (node (ref "BT1") (pin "+") (pinfunction "PLUS_+") (pintype "power_in"))
      (node (ref "U5") (pin "22") (pinfunction "V_BCKP_22") (pintype "passive"))
    )
    (net (code "27") (name "Net-(J3-CC1)") (class "Default")
      (node (ref "J3") (pin "A5") (pinfunction "CC1_A5") (pintype "bidirectional"))
      (node (ref "R12") (pin "1") (pinfunction "1_1") (pintype "passive"))
    )
    (net (code "28") (name "Net-(J3-CC2)") (class "Default")
      (node (ref "J3") (pin "B5") (pinfunction "CC2_B5") (pintype "bidirectional"))
      (node (ref "R15") (pin "2") (pinfunction "2_2") (pintype "passive"))
    )
    (net (code "29") (name "Net-(L1-P$1)") (class "Default")
      (node (ref "C44") (pin "1") (pinfunction "1_1") (pintype "passive"))
      (node (ref "C45") (pin "1") (pinfunction "1_1") (pintype "passive"))
      (node (ref "F3") (pin "1") (pinfunction "1_1") (pintype "passive"))
      (node (ref "L1") (pin "1") (pinfunction "P$1_1") (pintype "passive"))
      (node (ref "R17") (pin "2") (pinfunction "2_2") (pintype "passive"))
    )
    (net (code "30") (name "Net-(L1-P$2)") (class "Default")
      (node (ref "C35") (pin "2") (pinfunction "2_2") (pintype "passive"))
      (node (ref "L1") (pin "2") (pinfunction "P$2_2") (pintype "passive"))
      (node (ref "U10") (pin "2") (pinfunction "SW_2") (pintype "bidirectional"))
    )
    (net (code "31") (name "Net-(L2-P$1)") (class "Default")
      (node (ref "C16") (pin "1") (pinfunction "1_1") (pintype "passive"))
      (node (ref "C19") (pin "1") (pinfunction "1_1") (pintype "passive"))
      (node (ref "F1") (pin "1") (pinfunction "1_1") (pintype "passive"))
      (node (ref "L2") (pin "1") (pinfunction "P$1_1") (pintype "passive"))
      (node (ref "R2") (pin "2") (pinfunction "2_2") (pintype "passive"))
    )
    (net (code "32") (name "Net-(L2-P$2)") (class "Default")
      (node (ref "C17") (pin "2") (pinfunction "2_2") (pintype "passive"))
      (node (ref "L2") (pin "2") (pinfunction "P$2_2") (pintype "passive"))
      (node (ref "U7") (pin "2") (pinfunction "SW_2") (pintype "bidirectional"))
    )
    (net (code "33") (name "Net-(L4-P$2)") (class "Default")
      (node (ref "L4") (pin "2") (pinfunction "P$2_2") (pintype "passive"))
      (node (ref "U4") (pin "91") (pinfunction "VSW_91") (pintype "bidirectional"))
    )
    (net (code "34") (name "Net-(L5-P$1)") (class "Default")
      (node (ref "C61") (pin "1") (pinfunction "1_1") (pintype "passive"))
      (node (ref "C62") (pin "1") (pinfunction "1_1") (pintype "passive"))
      (node (ref "F5") (pin "1") (pinfunction "1_1") (pintype "passive"))
      (node (ref "L5") (pin "2") (pinfunction "P$1_2") (pintype "passive"))
      (node (ref "R31") (pin "2") (pinfunction "2_2") (pintype "passive"))
    )
    (net (code "35") (name "Net-(L5-P$2)") (class "Default")
      (node (ref "C64") (pin "2") (pinfunction "2_2") (pintype "passive"))
      (node (ref "L5") (pin "1") (pinfunction "P$2_1") (pintype "passive"))
      (node (ref "U12") (pin "2") (pinfunction "SW_2") (pintype "bidirectional"))
    )
    (net (code "36") (name "Net-(L6-P$1)") (class "Default")
      (node (ref "C6") (pin "1") (pinfunction "1_1") (pintype "passive"))
      (node (ref "C7") (pin "1") (pinfunction "1_1") (pintype "passive"))
      (node (ref "F6") (pin "1") (pinfunction "1_1") (pintype "passive"))
      (node (ref "L6") (pin "2") (pinfunction "P$1_2") (pintype "passive"))
      (node (ref "R30") (pin "2") (pinfunction "2_2") (pintype "passive"))
    )
    (net (code "37") (name "Net-(L6-P$2)") (class "Default")
      (node (ref "C65") (pin "2") (pinfunction "2_2") (pintype "passive"))
      (node (ref "L6") (pin "1") (pinfunction "P$2_1") (pintype "passive"))
      (node (ref "U13") (pin "2") (pinfunction "SW_2") (pintype "bidirectional"))
    )
    (net (code "38") (name "Net-(R26-Pad1)") (class "Default")
      (node (ref "R26") (pin "1") (pinfunction "1_1") (pintype "passive"))
      (node (ref "S1") (pin "A1") (pinfunction "P_A1") (pintype "passive"))
      (node (ref "S1") (pin "A2") (pinfunction "P_A2") (pintype "passive"))
    )
    (net (code "39") (name "Net-(R27-Pad1)") (class "Default")
      (node (ref "R27") (pin "1") (pinfunction "1_1") (pintype "passive"))
      (node (ref "R29") (pin "1") (pinfunction "1_1") (pintype "passive"))
      (node (ref "T1") (pin "B") (pinfunction "B_B") (pintype "passive"))
    )
    (net (code "40") (name "Net-(U1-OE)") (class "Default")
      (node (ref "R1") (pin "2") (pinfunction "2_2") (pintype "passive"))
      (node (ref "U1") (pin "8") (pinfunction "OE_8") (pintype "output"))
    )
    (net (code "41") (name "Net-(U7-BOOT)") (class "Default")
      (node (ref "C17") (pin "1") (pinfunction "1_1") (pintype "passive"))
      (node (ref "U7") (pin "6") (pinfunction "BOOT_6") (pintype "output"))
    )
    (net (code "42") (name "Net-(U7-FB)") (class "Default")
      (node (ref "R2") (pin "1") (pinfunction "1_1") (pintype "passive"))
      (node (ref "R3") (pin "2") (pinfunction "2_2") (pintype "passive"))
      (node (ref "U7") (pin "4") (pinfunction "FB_4") (pintype "input"))
    )
    (net (code "43") (name "Net-(U8-ADJ)") (class "Default")
      (node (ref "R14") (pin "1") (pinfunction "1_1") (pintype "passive"))
      (node (ref "R4") (pin "2") (pinfunction "2_2") (pintype "passive"))
      (node (ref "U8") (pin "4") (pinfunction "ADJ_4") (pintype "passive"))
    )
    (net (code "44") (name "Net-(U8-CMP1)") (class "Default")
      (node (ref "R4") (pin "1") (pinfunction "1_1") (pintype "passive"))
      (node (ref "R5") (pin "2") (pinfunction "2_2") (pintype "passive"))
      (node (ref "U8") (pin "3") (pinfunction "CMP1_3") (pintype "bidirectional"))
    )
    (net (code "45") (name "Net-(U8-CMP2)") (class "Default")
      (node (ref "R11") (pin "2") (pinfunction "2_2") (pintype "passive"))
      (node (ref "R13") (pin "1") (pinfunction "1_1") (pintype "passive"))
      (node (ref "U8") (pin "10") (pinfunction "CMP2_10") (pintype "bidirectional"))
    )
    (net (code "46") (name "Net-(U8-V1)") (class "Default")
      (node (ref "C36") (pin "1") (pinfunction "1_1") (pintype "passive"))
      (node (ref "F2") (pin "2") (pinfunction "2_2") (pintype "passive"))
      (node (ref "R14") (pin "2") (pinfunction "2_2") (pintype "passive"))
      (node (ref "U8") (pin "1") (pinfunction "V1_1") (pintype "bidirectional"))
    )
    (net (code "47") (name "Net-(U9-C1+)") (class "Default")
      (node (ref "C43") (pin "1") (pinfunction "1_1") (pintype "passive"))
      (node (ref "C47") (pin "1") (pinfunction "1_1") (pintype "passive"))
      (node (ref "U9") (pin "16") (pinfunction "C1+_16") (pintype "passive"))
    )
    (net (code "48") (name "Net-(U9-C1-)") (class "Default")
      (node (ref "C43") (pin "2") (pinfunction "2_2") (pintype "passive"))
      (node (ref "C47") (pin "2") (pinfunction "2_2") (pintype "passive"))
      (node (ref "U9") (pin "1") (pinfunction "C1-_1") (pintype "passive"))
    )
    (net (code "49") (name "Net-(U9-C2+)") (class "Default")
      (node (ref "C27") (pin "1") (pinfunction "1_1") (pintype "passive"))
      (node (ref "C30") (pin "1") (pinfunction "1_1") (pintype "passive"))
      (node (ref "U9") (pin "2") (pinfunction "C2+_2") (pintype "passive"))
    )
    (net (code "50") (name "Net-(U9-C2-)") (class "Default")
      (node (ref "C27") (pin "2") (pinfunction "2_2") (pintype "passive"))
      (node (ref "C30") (pin "2") (pinfunction "2_2") (pintype "passive"))
      (node (ref "U9") (pin "3") (pinfunction "C2-_3") (pintype "passive"))
    )
    (net (code "51") (name "Net-(U9-V+)") (class "Default")
      (node (ref "C49") (pin "1") (pinfunction "1_1") (pintype "passive"))
      (node (ref "C53") (pin "1") (pinfunction "1_1") (pintype "passive"))
      (node (ref "U9") (pin "15") (pinfunction "V+_15") (pintype "passive"))
    )
    (net (code "52") (name "Net-(U9-V-)") (class "Default")
      (node (ref "C1") (pin "1") (pinfunction "1_1") (pintype "passive"))
      (node (ref "C3") (pin "1") (pinfunction "1_1") (pintype "passive"))
      (node (ref "U9") (pin "4") (pinfunction "V-_4") (pintype "passive"))
    )
    (net (code "53") (name "Net-(U10-BOOT)") (class "Default")
      (node (ref "C35") (pin "1") (pinfunction "1_1") (pintype "passive"))
      (node (ref "U10") (pin "6") (pinfunction "BOOT_6") (pintype "output"))
    )
    (net (code "54") (name "Net-(U10-FB)") (class "Default")
      (node (ref "R16") (pin "2") (pinfunction "2_2") (pintype "passive"))
      (node (ref "R17") (pin "1") (pinfunction "1_1") (pintype "passive"))
      (node (ref "U10") (pin "4") (pinfunction "FB_4") (pintype "input"))
    )
    (net (code "55") (name "Net-(U11-G)") (class "Default")
      (node (ref "R24") (pin "1") (pinfunction "1_1") (pintype "passive"))
      (node (ref "U11") (pin "1") (pinfunction "G_1") (pintype "passive"))
    )
    (net (code "56") (name "Net-(U12-BOOT)") (class "Default")
      (node (ref "C64") (pin "1") (pinfunction "1_1") (pintype "passive"))
      (node (ref "U12") (pin "6") (pinfunction "BOOT_6") (pintype "output"))
    )
    (net (code "57") (name "Net-(U12-FB)") (class "Default")
      (node (ref "R31") (pin "1") (pinfunction "1_1") (pintype "passive"))
      (node (ref "R33") (pin "2") (pinfunction "2_2") (pintype "passive"))
      (node (ref "U12") (pin "4") (pinfunction "FB_4") (pintype "input"))
    )
    (net (code "58") (name "Net-(U13-BOOT)") (class "Default")
      (node (ref "C65") (pin "1") (pinfunction "1_1") (pintype "passive"))
      (node (ref "U13") (pin "6") (pinfunction "BOOT_6") (pintype "output"))
    )
    (net (code "59") (name "Net-(U13-FB)") (class "Default")
      (node (ref "R30") (pin "1") (pinfunction "1_1") (pintype "passive"))
      (node (ref "R32") (pin "2") (pinfunction "2_2") (pintype "passive"))
      (node (ref "U13") (pin "4") (pinfunction "FB_4") (pintype "input"))
    )
    (net (code "60") (name "PROBE") (class "Default")
      (node (ref "J2") (pin "10") (pinfunction "10_10") (pintype "passive"))
      (node (ref "J2") (pin "5") (pinfunction "5_5") (pintype "passive"))
      (node (ref "J8") (pin "10") (pinfunction "10_10") (pintype "passive"))
      (node (ref "J8") (pin "5") (pinfunction "5_5") (pintype "passive"))
      (node (ref "R27") (pin "2") (pinfunction "2_2") (pintype "passive"))
    )
    (net (code "61") (name "RAD_BUSY") (class "Default")
      (node (ref "U2") (pin "P$3") (pinfunction "BUSY_P$3") (pintype "passive"))
      (node (ref "U4") (pin "79") (pinfunction "PB23_79") (pintype "bidirectional"))
    )
    (net (code "62") (name "READY") (class "Default")
      (node (ref "U4") (pin "71") (pinfunction "PA21_71") (pintype "bidirectional"))
      (node (ref "U9") (pin "14") (pinfunction "READY_14") (pintype "passive"))
    )
    (net (code "63") (name "RREF+") (class "Default")
      (node (ref "J8") (pin "3") (pinfunction "3_3") (pintype "passive"))
      (node (ref "R34") (pin "1") (pinfunction "1_1") (pintype "passive"))
      (node (ref "U4") (pin "97") (pinfunction "PB00_97") (pintype "bidirectional"))
    )
    (net (code "64") (name "RSENSE+") (class "Default")
      (node (ref "J8") (pin "4") (pinfunction "4_4") (pintype "passive"))
      (node (ref "R35") (pin "1") (pinfunction "1_1") (pintype "passive"))
      (node (ref "U4") (pin "99") (pinfunction "PB02_99") (pintype "bidirectional"))
    )
    (net (code "65") (name "R_OUT") (class "Default")
      (node (ref "J2") (pin "3") (pinfunction "3_3") (pintype "passive"))
      (node (ref "U9") (pin "6") (pinfunction "ROUT_6") (pintype "passive"))
    )
    (net (code "66") (name "SCLK_1") (class "Default")
      (node (ref "U4") (pin "81") (pinfunction "PB25_81") (pintype "bidirectional"))
      (node (ref "U5") (pin "19") (pinfunction "SCL/SPI_CLK_19") (pintype "passive"))
      (node (ref "U6") (pin "4") (pinfunction "SCK_4") (pintype "passive"))
    )
    (net (code "67") (name "SCLK_2") (class "Default")
      (node (ref "U2") (pin "P$6") (pinfunction "SCK_P$6") (pintype "passive"))
      (node (ref "U3") (pin "13") (pinfunction "AP_SCL/AP_SCLK_13") (pintype "passive"))
      (node (ref "U4") (pin "53") (pinfunction "PA17_53") (pintype "bidirectional"))
    )
    (net (code "68") (name "SD_CD") (class "Default")
      (node (ref "J1") (pin "2") (pinfunction "CD/DAT3_2") (pintype "passive"))
      (node (ref "R7") (pin "1") (pinfunction "1_1") (pintype "passive"))
      (node (ref "U4") (pin "19") (pinfunction "PA06_19") (pintype "bidirectional"))
    )
    (net (code "69") (name "SD_CK") (class "Default")
      (node (ref "J1") (pin "5") (pinfunction "CLK_5") (pintype "passive"))
      (node (ref "U4") (pin "33") (pinfunction "PB11_33") (pintype "bidirectional"))
    )
    (net (code "70") (name "SD_CMD") (class "Default")
      (node (ref "J1") (pin "3") (pinfunction "CMD_3") (pintype "passive"))
      (node (ref "R8") (pin "1") (pinfunction "1_1") (pintype "passive"))
      (node (ref "U4") (pin "26") (pinfunction "PA08_26") (pintype "bidirectional"))
    )
    (net (code "71") (name "SD_DATA0") (class "Default")
      (node (ref "J1") (pin "7") (pinfunction "DAT0_7") (pintype "passive"))
      (node (ref "R9") (pin "1") (pinfunction "1_1") (pintype "passive"))
      (node (ref "U4") (pin "27") (pinfunction "PA09_27") (pintype "bidirectional"))
    )
    (net (code "72") (name "SD_DATA1") (class "Default")
      (node (ref "J1") (pin "8") (pinfunction "DAT1_8") (pintype "passive"))
      (node (ref "R10") (pin "1") (pinfunction "1_1") (pintype "passive"))
      (node (ref "U4") (pin "28") (pinfunction "PA10_28") (pintype "bidirectional"))
    )
    (net (code "73") (name "SD_DATA2") (class "Default")
      (node (ref "J1") (pin "1") (pinfunction "DATA2_1") (pintype "passive"))
      (node (ref "R6") (pin "1") (pinfunction "1_1") (pintype "passive"))
      (node (ref "U4") (pin "29") (pinfunction "PA11_29") (pintype "bidirectional"))
    )
    (net (code "74") (name "SOLENOID") (class "Default")
      (node (ref "D1") (pin "1") (pinfunction "A_1") (pintype "passive"))
      (node (ref "R23") (pin "2") (pinfunction "2_2") (pintype "passive"))
      (node (ref "R24") (pin "2") (pinfunction "2_2") (pintype "passive"))
      (node (ref "U4") (pin "37") (pinfunction "PB15_37") (pintype "bidirectional"))
    )
    (net (code "75") (name "SOL_TRIG") (class "Default")
      (node (ref "CR1") (pin "2") (pinfunction "12_2") (pintype "passive"))
      (node (ref "J7") (pin "3") (pinfunction "3_3") (pintype "passive"))
      (node (ref "U11") (pin "3") (pinfunction "D_3") (pintype "passive"))
    )
    (net (code "76") (name "SWCLK") (class "Default")
      (node (ref "J5") (pin "4") (pinfunction "SWCLK/TCK_4") (pintype "bidirectional"))
      (node (ref "R18") (pin "2") (pinfunction "2_2") (pintype "passive"))
      (node (ref "U4") (pin "93") (pinfunction "PA30_93") (pintype "bidirectional"))
    )
    (net (code "77") (name "SWDIO") (class "Default")
      (node (ref "J5") (pin "2") (pinfunction "SWIO/TMS_2") (pintype "bidirectional"))
      (node (ref "U4") (pin "94") (pinfunction "PA31_94") (pintype "bidirectional"))
    )
    (net (code "78") (name "TX_READY") (class "Default")
      (node (ref "U4") (pin "78") (pinfunction "PB22_78") (pintype "bidirectional"))
      (node (ref "U5") (pin "4") (pinfunction "EXTINT_4") (pintype "passive"))
    )
    (net (code "79") (name "T_OUT") (class "Default")
      (node (ref "J2") (pin "4") (pinfunction "4_4") (pintype "passive"))
      (node (ref "U9") (pin "10") (pinfunction "TOUT_10") (pintype "passive"))
    )
    (net (code "80") (name "UART_RX_CTD_A") (class "Default")
      (node (ref "U1") (pin "5") (pinfunction "A4_5") (pintype "bidirectional"))
      (node (ref "U4") (pin "34") (pinfunction "PB12_34") (pintype "bidirectional"))
    )
    (net (code "81") (name "UART_RX_CTD_B") (class "Default")
      (node (ref "J2") (pin "6") (pinfunction "6_6") (pintype "passive"))
      (node (ref "U1") (pin "10") (pinfunction "B4_10") (pintype "bidirectional"))
    )
    (net (code "82") (name "UART_RX_M_A") (class "Default")
      (node (ref "U1") (pin "3") (pinfunction "A2_3") (pintype "bidirectional"))
      (node (ref "U4") (pin "64") (pinfunction "PB16_64") (pintype "bidirectional"))
    )
    (net (code "83") (name "UART_RX_M_B") (class "Default")
      (node (ref "J7") (pin "4") (pinfunction "4_4") (pintype "passive"))
      (node (ref "U1") (pin "12") (pinfunction "B2_12") (pintype "bidirectional"))
    )
    (net (code "84") (name "UART_RX_PH") (class "Default")
      (node (ref "J2") (pin "2") (pinfunction "2_2") (pintype "passive"))
      (node (ref "U4") (pin "46") (pinfunction "PA12_46") (pintype "bidirectional"))
    )
    (net (code "85") (name "UART_TX_CTD_A") (class "Default")
      (node (ref "U1") (pin "4") (pinfunction "A3_4") (pintype "bidirectional"))
      (node (ref "U4") (pin "35") (pinfunction "PB13_35") (pintype "bidirectional"))
    )
    (net (code "86") (name "UART_TX_CTD_B") (class "Default")
      (node (ref "J2") (pin "7") (pinfunction "7_7") (pintype "passive"))
      (node (ref "U1") (pin "11") (pinfunction "B3_11") (pintype "bidirectional"))
    )
    (net (code "87") (name "UART_TX_M_A") (class "Default")
      (node (ref "U1") (pin "2") (pinfunction "A1_2") (pintype "bidirectional"))
      (node (ref "U4") (pin "65") (pinfunction "PB17_65") (pintype "bidirectional"))
    )
    (net (code "88") (name "UART_TX_M_B") (class "Default")
      (node (ref "J7") (pin "5") (pinfunction "5_5") (pintype "passive"))
      (node (ref "U1") (pin "13") (pinfunction "B1_13") (pintype "bidirectional"))
    )
    (net (code "89") (name "UART_TX_PH") (class "Default")
      (node (ref "J2") (pin "1") (pinfunction "1_1") (pintype "passive"))
      (node (ref "U4") (pin "47") (pinfunction "PA13_47") (pintype "bidirectional"))
    )
    (net (code "90") (name "VBATT") (class "Default")
      (node (ref "$$$$$$U$3") (pin "P$1") (pinfunction "P$1_P$1") (pintype "bidirectional"))
      (node (ref "C10") (pin "+") (pinfunction "+_+") (pintype "passive"))
      (node (ref "C11") (pin "1") (pinfunction "1_1") (pintype "passive"))
      (node (ref "C12") (pin "1") (pinfunction "1_1") (pintype "passive"))
      (node (ref "C2") (pin "2") (pinfunction "2_2") (pintype "passive"))
      (node (ref "C8") (pin "+") (pinfunction "+_+") (pintype "passive"))
      (node (ref "C9") (pin "2") (pinfunction "2_2") (pintype "passive"))
      (node (ref "F4") (pin "1") (pinfunction "1_1") (pintype "passive"))
      (node (ref "J7") (pin "10") (pinfunction "10_10") (pintype "passive"))
      (node (ref "R22") (pin "2") (pinfunction "2_2") (pintype "passive"))
      (node (ref "U10") (pin "3") (pinfunction "VIN_3") (pintype "input"))
      (node (ref "U13") (pin "3") (pinfunction "VIN_3") (pintype "input"))
      (node (ref "U7") (pin "3") (pinfunction "VIN_3") (pintype "input"))
    )
    (net (code "91") (name "VBATT_5V") (class "Default")
      (node (ref "$$$$$$U$2") (pin "P$1") (pinfunction "P$1_P$1") (pintype "bidirectional"))
      (node (ref "C29") (pin "1") (pinfunction "1_1") (pintype "passive"))
      (node (ref "F3") (pin "2") (pinfunction "2_2") (pintype "passive"))
      (node (ref "R13") (pin "2") (pinfunction "2_2") (pintype "passive"))
      (node (ref "U8") (pin "12") (pinfunction "V2_12") (pintype "bidirectional"))
    )
    (net (code "92") (name "VBUS") (class "Default")
      (node (ref "$$$$$$U$1") (pin "P$1") (pinfunction "P$1_P$1") (pintype "bidirectional"))
      (node (ref "F2") (pin "1") (pinfunction "1_1") (pintype "passive"))
      (node (ref "J3") (pin "A4/B9") (pinfunction "VBUS_A4/B9") (pintype "power_in"))
      (node (ref "J3") (pin "B4/A9") (pinfunction "VBUS_B4/A9") (pintype "power_in"))
    )
    (net (code "93") (name "VCCA") (class "Default")
      (node (ref "C48") (pin "1") (pinfunction "1_1") (pintype "passive"))
      (node (ref "C51") (pin "1") (pinfunction "1_1") (pintype "passive"))
      (node (ref "L3") (pin "2") (pinfunction "2_2") (pintype "passive"))
      (node (ref "U4") (pin "12") (pinfunction "VDDANA_12") (pintype "power_in"))
    )
    (net (code "94") (name "VCC_CORE") (class "Default")
      (node (ref "C50") (pin "1") (pinfunction "1_1") (pintype "passive"))
      (node (ref "C54") (pin "1") (pinfunction "1_1") (pintype "passive"))
      (node (ref "L4") (pin "1") (pinfunction "P$1_1") (pintype "passive"))
      (node (ref "U4") (pin "89") (pinfunction "VDDCORE_89") (pintype "power_in"))
    )
    (net (code "95") (name "VIN") (class "Default")
      (node (ref "$$$$$$U$6") (pin "P$1") (pinfunction "P$1_P$1") (pintype "bidirectional"))
      (node (ref "F4") (pin "2") (pinfunction "2_2") (pintype "passive"))
      (node (ref "J8") (pin "1") (pinfunction "1_1") (pintype "passive"))
    )
    (net (code "96") (name "XIN32") (class "Default")
      (node (ref "C52") (pin "1") (pinfunction "1_1") (pintype "passive"))
      (node (ref "U4") (pin "1") (pinfunction "PA00_1") (pintype "bidirectional"))
      (node (ref "Y1") (pin "1") (pinfunction "1_1") (pintype "passive"))
    )
    (net (code "97") (name "XOUT32") (class "Default")
      (node (ref "C41") (pin "1") (pinfunction "1_1") (pintype "passive"))
      (node (ref "U4") (pin "2") (pinfunction "PA01_2") (pintype "bidirectional"))
      (node (ref "Y1") (pin "4") (pinfunction "2_4") (pintype "passive"))
    )
    (net (code "98") (name "unconnected-(J1-DETECT-PadDT)") (class "Default")
      (node (ref "J1") (pin "DT") (pinfunction "DETECT_DT") (pintype "passive"))
    )
    (net (code "99") (name "unconnected-(J1-SWITCH-PadSW)") (class "Default")
      (node (ref "J1") (pin "SW") (pinfunction "SWITCH_SW") (pintype "passive"))
    )
    (net (code "100") (name "unconnected-(J2-Pad8)") (class "Default")
      (node (ref "J2") (pin "8") (pinfunction "8_8") (pintype "passive"))
    )
    (net (code "101") (name "unconnected-(J3-SBU1-PadA8)") (class "Default")
      (node (ref "J3") (pin "A8") (pinfunction "SBU1_A8") (pintype "bidirectional"))
    )
    (net (code "102") (name "unconnected-(J3-SBU2-PadB8)") (class "Default")
      (node (ref "J3") (pin "B8") (pinfunction "SBU2_B8") (pintype "bidirectional"))
    )
    (net (code "103") (name "unconnected-(J5-GNDDETECT-Pad9)") (class "Default")
      (node (ref "J5") (pin "9") (pinfunction "GNDDETECT_9") (pintype "bidirectional"))
    )
    (net (code "104") (name "unconnected-(J5-SWO{slash}TDO-Pad6)") (class "Default")
      (node (ref "J5") (pin "6") (pinfunction "SWO/TDO_6") (pintype "bidirectional"))
    )
    (net (code "105") (name "unconnected-(J5-TDI-Pad8)") (class "Default")
      (node (ref "J5") (pin "8") (pinfunction "TDI_8") (pintype "bidirectional"))
    )
    (net (code "106") (name "unconnected-(J8-Pad2)") (class "Default")
      (node (ref "J8") (pin "2") (pinfunction "2_2") (pintype "passive"))
    )
    (net (code "107") (name "unconnected-(J8-Pad6)") (class "Default")
      (node (ref "J8") (pin "6") (pinfunction "6_6") (pintype "passive"))
    )
    (net (code "108") (name "unconnected-(J8-Pad7)") (class "Default")
      (node (ref "J8") (pin "7") (pinfunction "7_7") (pintype "passive"))
    )
    (net (code "109") (name "unconnected-(U1-NC-Pad9)") (class "Default")
      (node (ref "U1") (pin "9") (pinfunction "NC_9") (pintype "passive"))
    )
    (net (code "110") (name "unconnected-(U1-NC_2-Pad6)") (class "Default")
      (node (ref "U1") (pin "6") (pinfunction "NC_2_6") (pintype "passive"))
    )
    (net (code "111") (name "unconnected-(U2-DIO1-PadP$4)") (class "Default")
      (node (ref "U2") (pin "P$4") (pinfunction "DIO1_P$4") (pintype "passive"))
    )
    (net (code "112") (name "unconnected-(U3-INT2{slash}FSYNC{slash}CLKIN-Pad9)") (class "Default")
      (node (ref "U3") (pin "9") (pinfunction "INT2/FSYNC/CLKIN_9") (pintype "passive"))
    )
    (net (code "113") (name "unconnected-(U4-PA02-Pad7)") (class "Default")
      (node (ref "U4") (pin "7") (pinfunction "PA02_7") (pintype "bidirectional"))
    )
    (net (code "114") (name "unconnected-(U4-PA03-Pad8)") (class "Default")
      (node (ref "U4") (pin "8") (pinfunction "PA03_8") (pintype "bidirectional"))
    )
    (net (code "115") (name "unconnected-(U4-PA04-Pad17)") (class "Default")
      (node (ref "U4") (pin "17") (pinfunction "PA04_17") (pintype "bidirectional"))
    )
    (net (code "116") (name "unconnected-(U4-PA05-Pad18)") (class "Default")
      (node (ref "U4") (pin "18") (pinfunction "PA05_18") (pintype "bidirectional"))
    )
    (net (code "117") (name "unconnected-(U4-PA07-Pad20)") (class "Default")
      (node (ref "U4") (pin "20") (pinfunction "PA07_20") (pintype "bidirectional"))
    )
    (net (code "118") (name "unconnected-(U4-PA20-Pad70)") (class "Default")
      (node (ref "U4") (pin "70") (pinfunction "PA20_70") (pintype "bidirectional"))
    )
    (net (code "119") (name "unconnected-(U4-PA27-Pad87)") (class "Default")
      (node (ref "U4") (pin "87") (pinfunction "PA27_87") (pintype "bidirectional"))
    )
    (net (code "120") (name "unconnected-(U4-PB01-Pad98)") (class "Default")
      (node (ref "U4") (pin "98") (pinfunction "PB01_98") (pintype "bidirectional"))
    )
    (net (code "121") (name "unconnected-(U4-PB03-Pad100)") (class "Default")
      (node (ref "U4") (pin "100") (pinfunction "PB03_100") (pintype "bidirectional"))
    )
    (net (code "122") (name "unconnected-(U4-PB04-Pad9)") (class "Default")
      (node (ref "U4") (pin "9") (pinfunction "PB04_9") (pintype "bidirectional"))
    )
    (net (code "123") (name "unconnected-(U4-PB05-Pad10)") (class "Default")
      (node (ref "U4") (pin "10") (pinfunction "PB05_10") (pintype "bidirectional"))
    )
    (net (code "124") (name "unconnected-(U4-PB07-Pad14)") (class "Default")
      (node (ref "U4") (pin "14") (pinfunction "PB07_14") (pintype "bidirectional"))
    )
    (net (code "125") (name "unconnected-(U4-PB09-Pad16)") (class "Default")
      (node (ref "U4") (pin "16") (pinfunction "PB09_16") (pintype "bidirectional"))
    )
    (net (code "126") (name "unconnected-(U4-PB10-Pad32)") (class "Default")
      (node (ref "U4") (pin "32") (pinfunction "PB10_32") (pintype "bidirectional"))
    )
    (net (code "127") (name "unconnected-(U4-PB18-Pad66)") (class "Default")
      (node (ref "U4") (pin "66") (pinfunction "PB18_66") (pintype "bidirectional"))
    )
    (net (code "128") (name "unconnected-(U4-PB19-Pad67)") (class "Default")
      (node (ref "U4") (pin "67") (pinfunction "PB19_67") (pintype "bidirectional"))
    )
    (net (code "129") (name "unconnected-(U4-PB30-Pad95)") (class "Default")
      (node (ref "U4") (pin "95") (pinfunction "PB30_95") (pintype "bidirectional"))
    )
    (net (code "130") (name "unconnected-(U4-PB31-Pad96)") (class "Default")
      (node (ref "U4") (pin "96") (pinfunction "PB31_96") (pintype "bidirectional"))
    )
    (net (code "131") (name "unconnected-(U4-PC00-Pad3)") (class "Default")
      (node (ref "U4") (pin "3") (pinfunction "PC00_3") (pintype "bidirectional"))
    )
    (net (code "132") (name "unconnected-(U4-PC01-Pad4)") (class "Default")
      (node (ref "U4") (pin "4") (pinfunction "PC01_4") (pintype "bidirectional"))
    )
    (net (code "133") (name "unconnected-(U4-PC02-Pad5)") (class "Default")
      (node (ref "U4") (pin "5") (pinfunction "PC02_5") (pintype "bidirectional"))
    )
    (net (code "134") (name "unconnected-(U4-PC03-Pad6)") (class "Default")
      (node (ref "U4") (pin "6") (pinfunction "PC03_6") (pintype "bidirectional"))
    )
    (net (code "135") (name "unconnected-(U4-PC05-Pad21)") (class "Default")
      (node (ref "U4") (pin "21") (pinfunction "PC05_21") (pintype "bidirectional"))
    )
    (net (code "136") (name "unconnected-(U4-PC06-Pad22)") (class "Default")
      (node (ref "U4") (pin "22") (pinfunction "PC06_22") (pintype "bidirectional"))
    )
    (net (code "137") (name "unconnected-(U4-PC07-Pad23)") (class "Default")
      (node (ref "U4") (pin "23") (pinfunction "PC07_23") (pintype "bidirectional"))
    )
    (net (code "138") (name "unconnected-(U4-PC10-Pad40)") (class "Default")
      (node (ref "U4") (pin "40") (pinfunction "PC10_40") (pintype "bidirectional"))
    )
    (net (code "139") (name "unconnected-(U4-PC11-Pad41)") (class "Default")
      (node (ref "U4") (pin "41") (pinfunction "PC11_41") (pintype "bidirectional"))
    )
    (net (code "140") (name "unconnected-(U4-PC12-Pad42)") (class "Default")
      (node (ref "U4") (pin "42") (pinfunction "PC12_42") (pintype "bidirectional"))
    )
    (net (code "141") (name "unconnected-(U4-PC13-Pad43)") (class "Default")
      (node (ref "U4") (pin "43") (pinfunction "PC13_43") (pintype "bidirectional"))
    )
    (net (code "142") (name "unconnected-(U4-PC14-Pad44)") (class "Default")
      (node (ref "U4") (pin "44") (pinfunction "PC14_44") (pintype "bidirectional"))
    )
    (net (code "143") (name "unconnected-(U4-PC15-Pad45)") (class "Default")
      (node (ref "U4") (pin "45") (pinfunction "PC15_45") (pintype "bidirectional"))
    )
    (net (code "144") (name "unconnected-(U4-PC19-Pad59)") (class "Default")
      (node (ref "U4") (pin "59") (pinfunction "PC19_59") (pintype "bidirectional"))
    )
    (net (code "145") (name "unconnected-(U4-PC20-Pad60)") (class "Default")
      (node (ref "U4") (pin "60") (pinfunction "PC20_60") (pintype "bidirectional"))
    )
    (net (code "146") (name "unconnected-(U4-PC21-Pad61)") (class "Default")
      (node (ref "U4") (pin "61") (pinfunction "PC21_61") (pintype "bidirectional"))
    )
    (net (code "147") (name "unconnected-(U4-PC26-Pad84)") (class "Default")
      (node (ref "U4") (pin "84") (pinfunction "PC26_84") (pintype "bidirectional"))
    )
    (net (code "148") (name "unconnected-(U4-PC27-Pad85)") (class "Default")
      (node (ref "U4") (pin "85") (pinfunction "PC27_85") (pintype "bidirectional"))
    )
    (net (code "149") (name "unconnected-(U4-PC28-Pad86)") (class "Default")
      (node (ref "U4") (pin "86") (pinfunction "PC28_86") (pintype "bidirectional"))
    )
    (net (code "150") (name "unconnected-(U5-SAFEBOOT_N-Pad1)") (class "Default")
      (node (ref "U5") (pin "1") (pinfunction "SAFEBOOT_N_1") (pintype "passive"))
    )
    (net (code "151") (name "unconnected-(U5-TIMEPULSE-Pad3)") (class "Default")
      (node (ref "U5") (pin "3") (pinfunction "TIMEPULSE_3") (pintype "passive"))
    )
    (net (code "152") (name "unconnected-(U5-USB_DM-Pad5)") (class "Default")
      (node (ref "U5") (pin "5") (pinfunction "USB_DM_5") (pintype "passive"))
    )
    (net (code "153") (name "unconnected-(U5-USB_DP-Pad6)") (class "Default")
      (node (ref "U5") (pin "6") (pinfunction "USB_DP_6") (pintype "passive"))
    )
    (net (code "154") (name "unconnected-(U5-VCC_RF-Pad9)") (class "Default")
      (node (ref "U5") (pin "9") (pinfunction "VCC_RF_9") (pintype "passive"))
    )
    (net (code "155") (name "unconnected-(U7-EN-Pad5)") (class "Default")
      (node (ref "U7") (pin "5") (pinfunction "EN_5") (pintype "input"))
    )
    (net (code "156") (name "unconnected-(U8-CMPOUT1-Pad6)") (class "Default")
      (node (ref "U8") (pin "6") (pinfunction "CMPOUT1_6") (pintype "output"))
    )
    (net (code "157") (name "unconnected-(U8-CMPOUT2-Pad7)") (class "Default")
      (node (ref "U8") (pin "7") (pinfunction "CMPOUT2_7") (pintype "output"))
    )
    (net (code "158") (name "unconnected-(U8-V2ON-Pad8)") (class "Default")
      (node (ref "U8") (pin "8") (pinfunction "V2ON_8") (pintype "passive"))
    )
    (net (code "159") (name "unconnected-(U10-EN-Pad5)") (class "Default")
      (node (ref "U10") (pin "5") (pinfunction "EN_5") (pintype "input"))
    )
    (net (code "160") (name "unconnected-(U12-EN-Pad5)") (class "Default")
      (node (ref "U12") (pin "5") (pinfunction "EN_5") (pintype "input"))
    )
    (net (code "161") (name "unconnected-(U13-EN-Pad5)") (class "Default")
      (node (ref "U13") (pin "5") (pinfunction "EN_5") (pintype "input"))
    )
    (net (code "162") (name "~{RESET_N}") (class "Default")
      (node (ref "U4") (pin "72") (pinfunction "PA22_72") (pintype "bidirectional"))
      (node (ref "U5") (pin "8") (pinfunction "RESET_N_8") (pintype "passive"))
    )
    (net (code "163") (name "~{RESET}") (class "Default")
      (node (ref "C58") (pin "1") (pinfunction "1_1") (pintype "passive"))
      (node (ref "J5") (pin "10") (pinfunction "~{RST}_10") (pintype "bidirectional"))
      (node (ref "R25") (pin "1") (pinfunction "1_1") (pintype "passive"))
      (node (ref "R26") (pin "2") (pinfunction "2_2") (pintype "passive"))
      (node (ref "U4") (pin "88") (pinfunction "RESETN_88") (pintype "input"))
    )
    (net (code "164") (name "~{SX-NRESET}") (class "Default")
      (node (ref "U2") (pin "P$2") (pinfunction "SX-NRESET_P$2") (pintype "passive"))
      (node (ref "U4") (pin "68") (pinfunction "PB20_68") (pintype "bidirectional"))
    )
  )
)
